# ProProject_AT_START_L021_V1_0.net
KiCad netlist of a schematic drawn in EasyEDA Pro
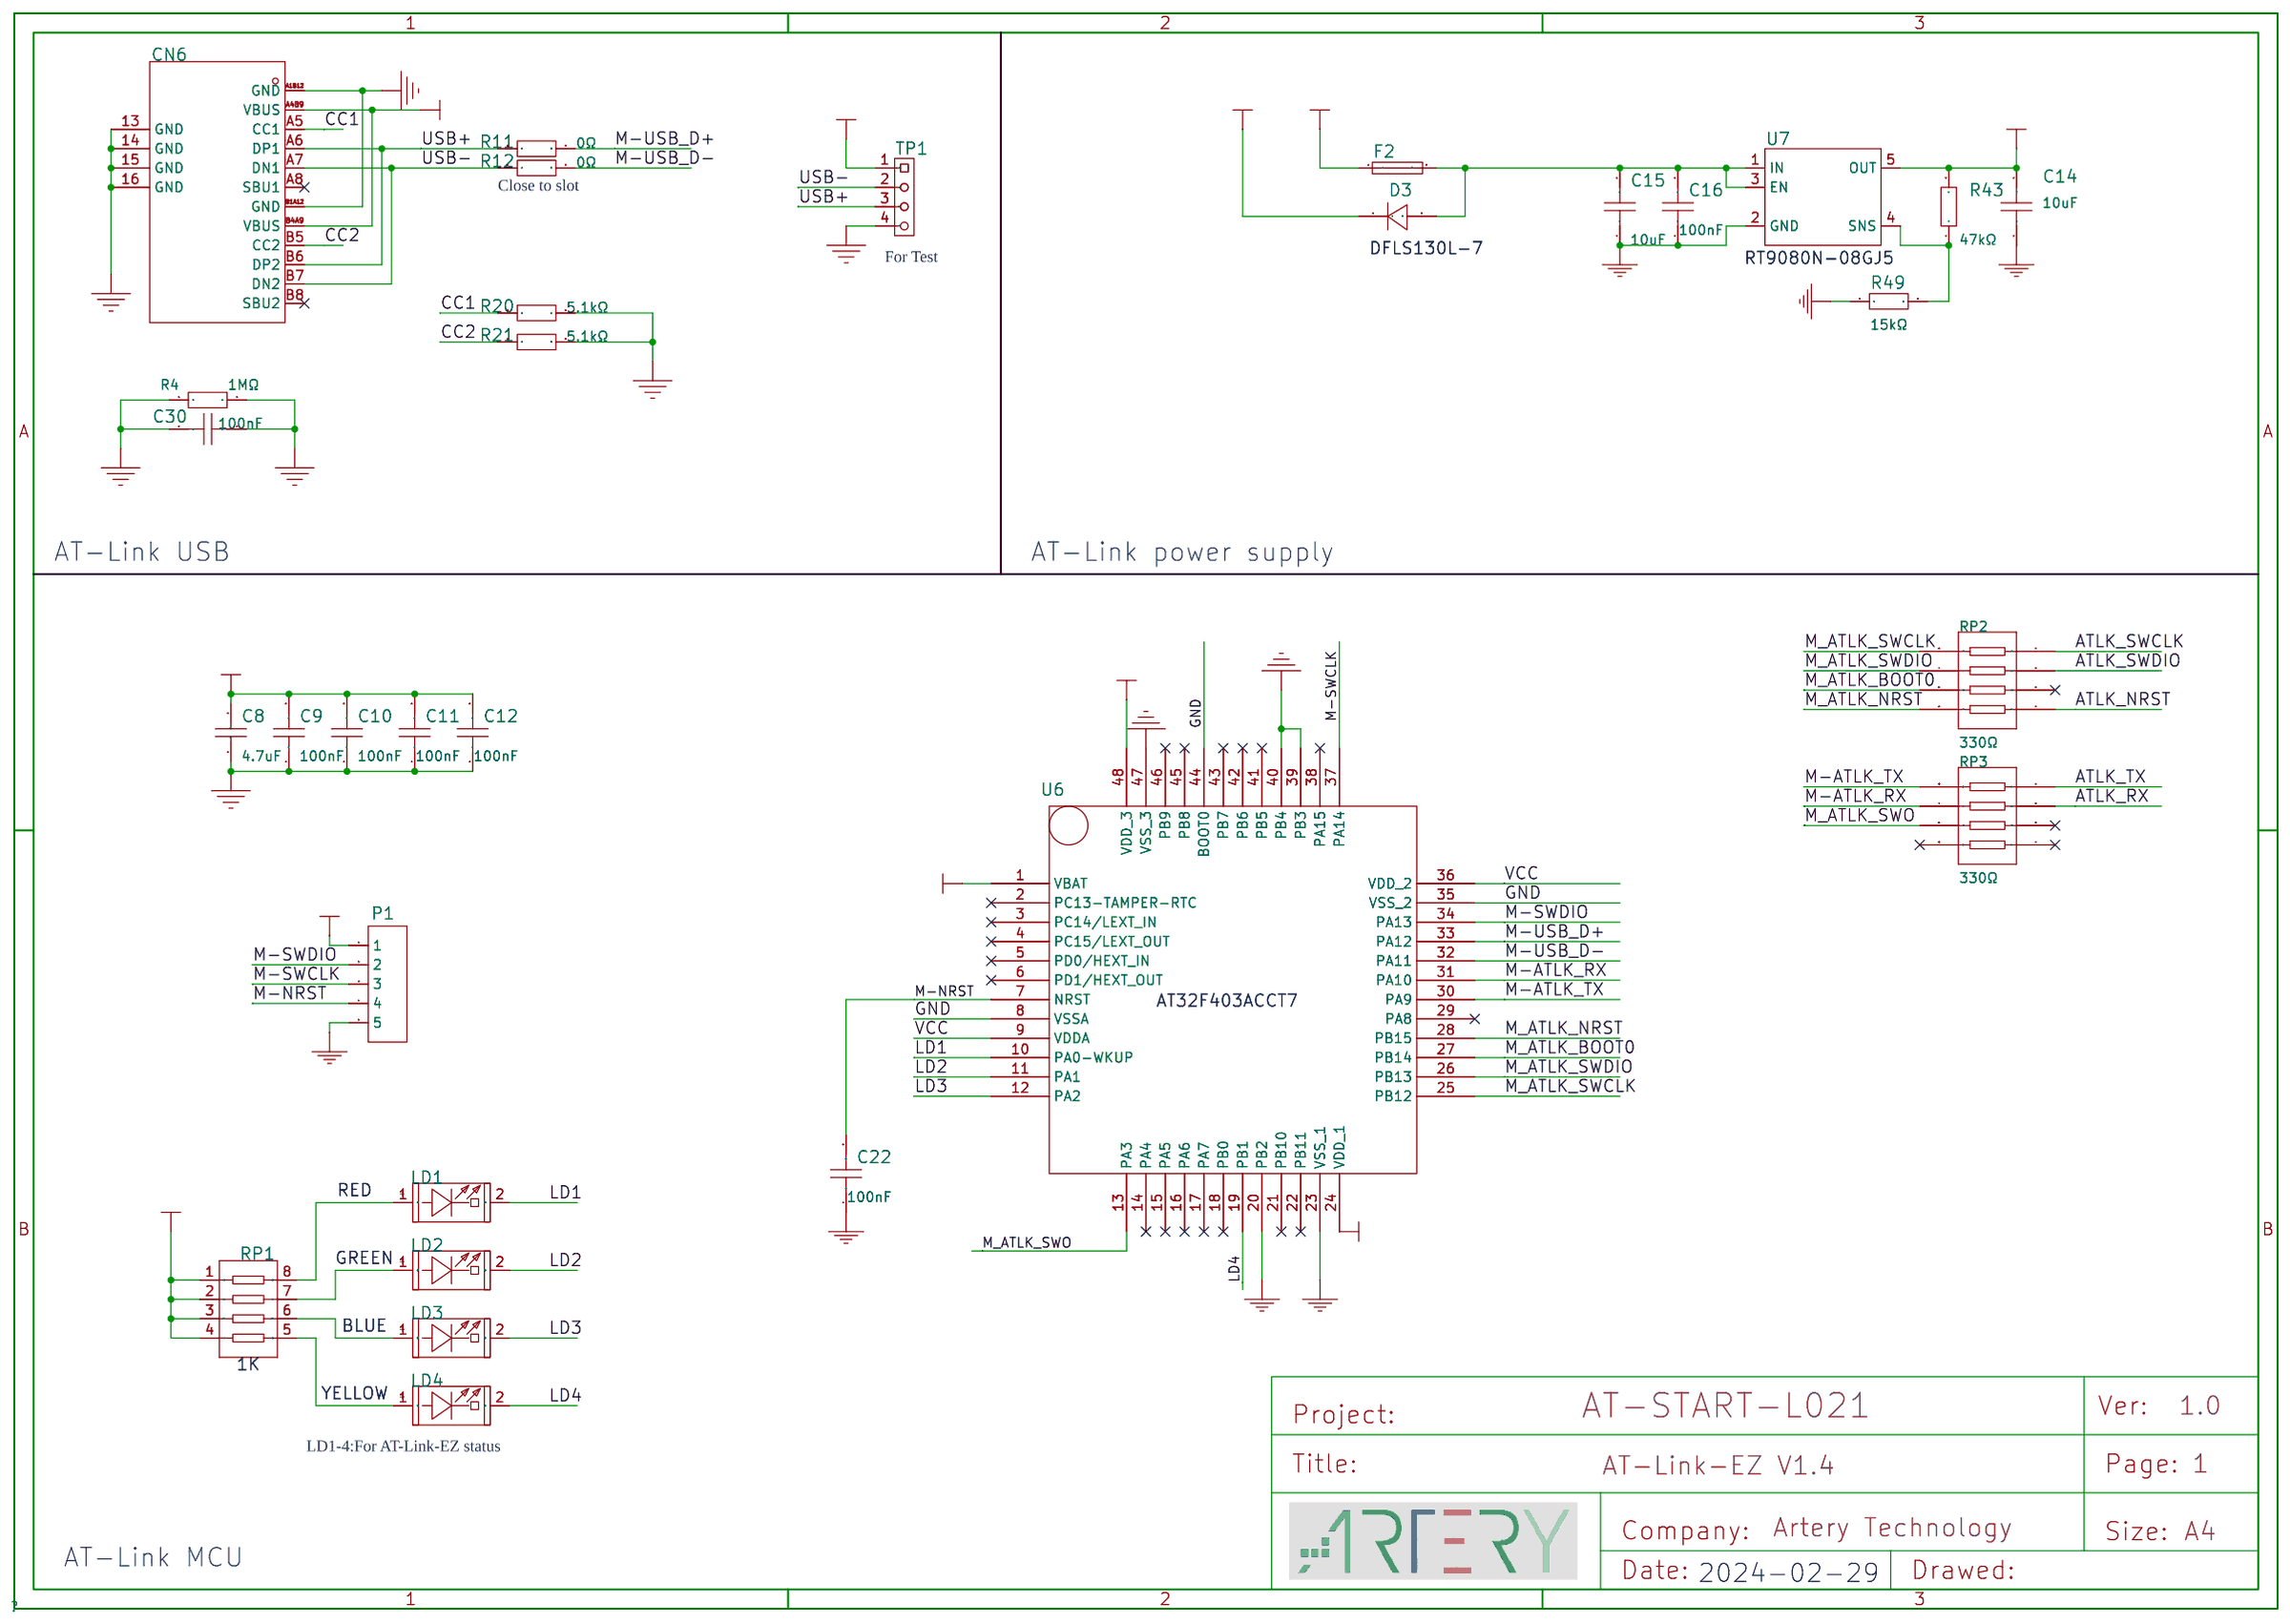
[diagram p0: AT-Link-EZ V1.4]
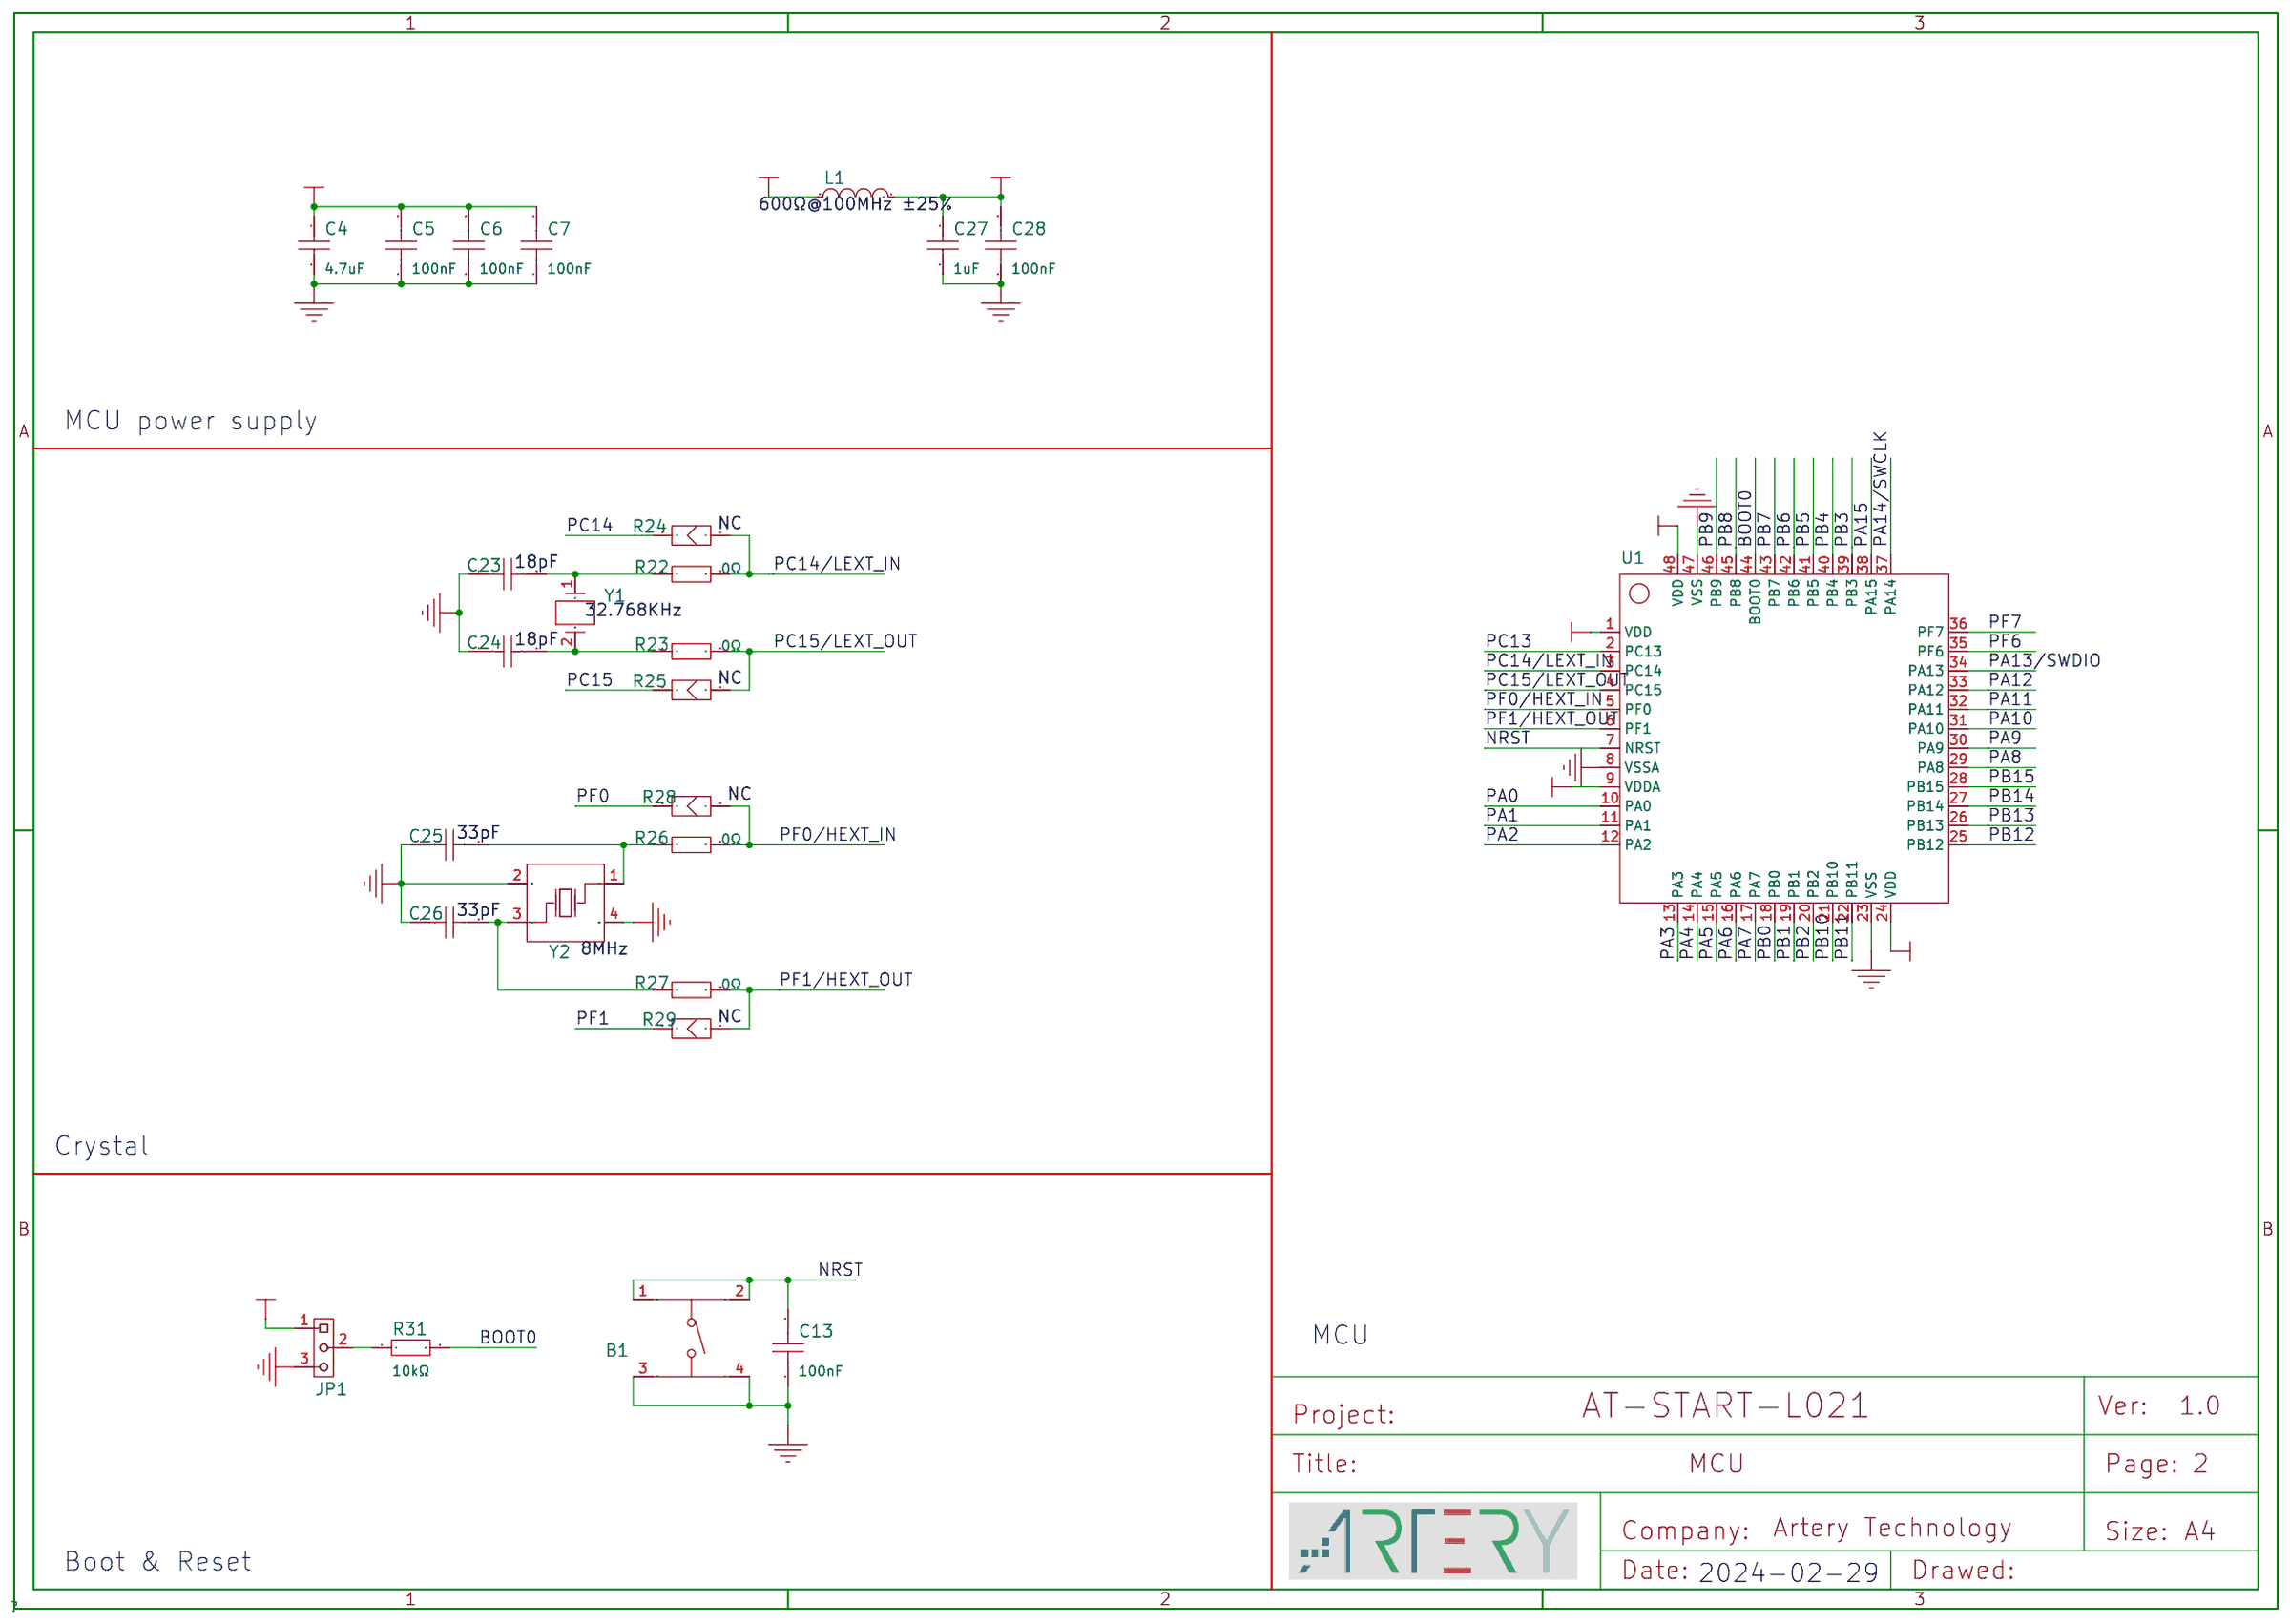
[diagram p1: MCU]
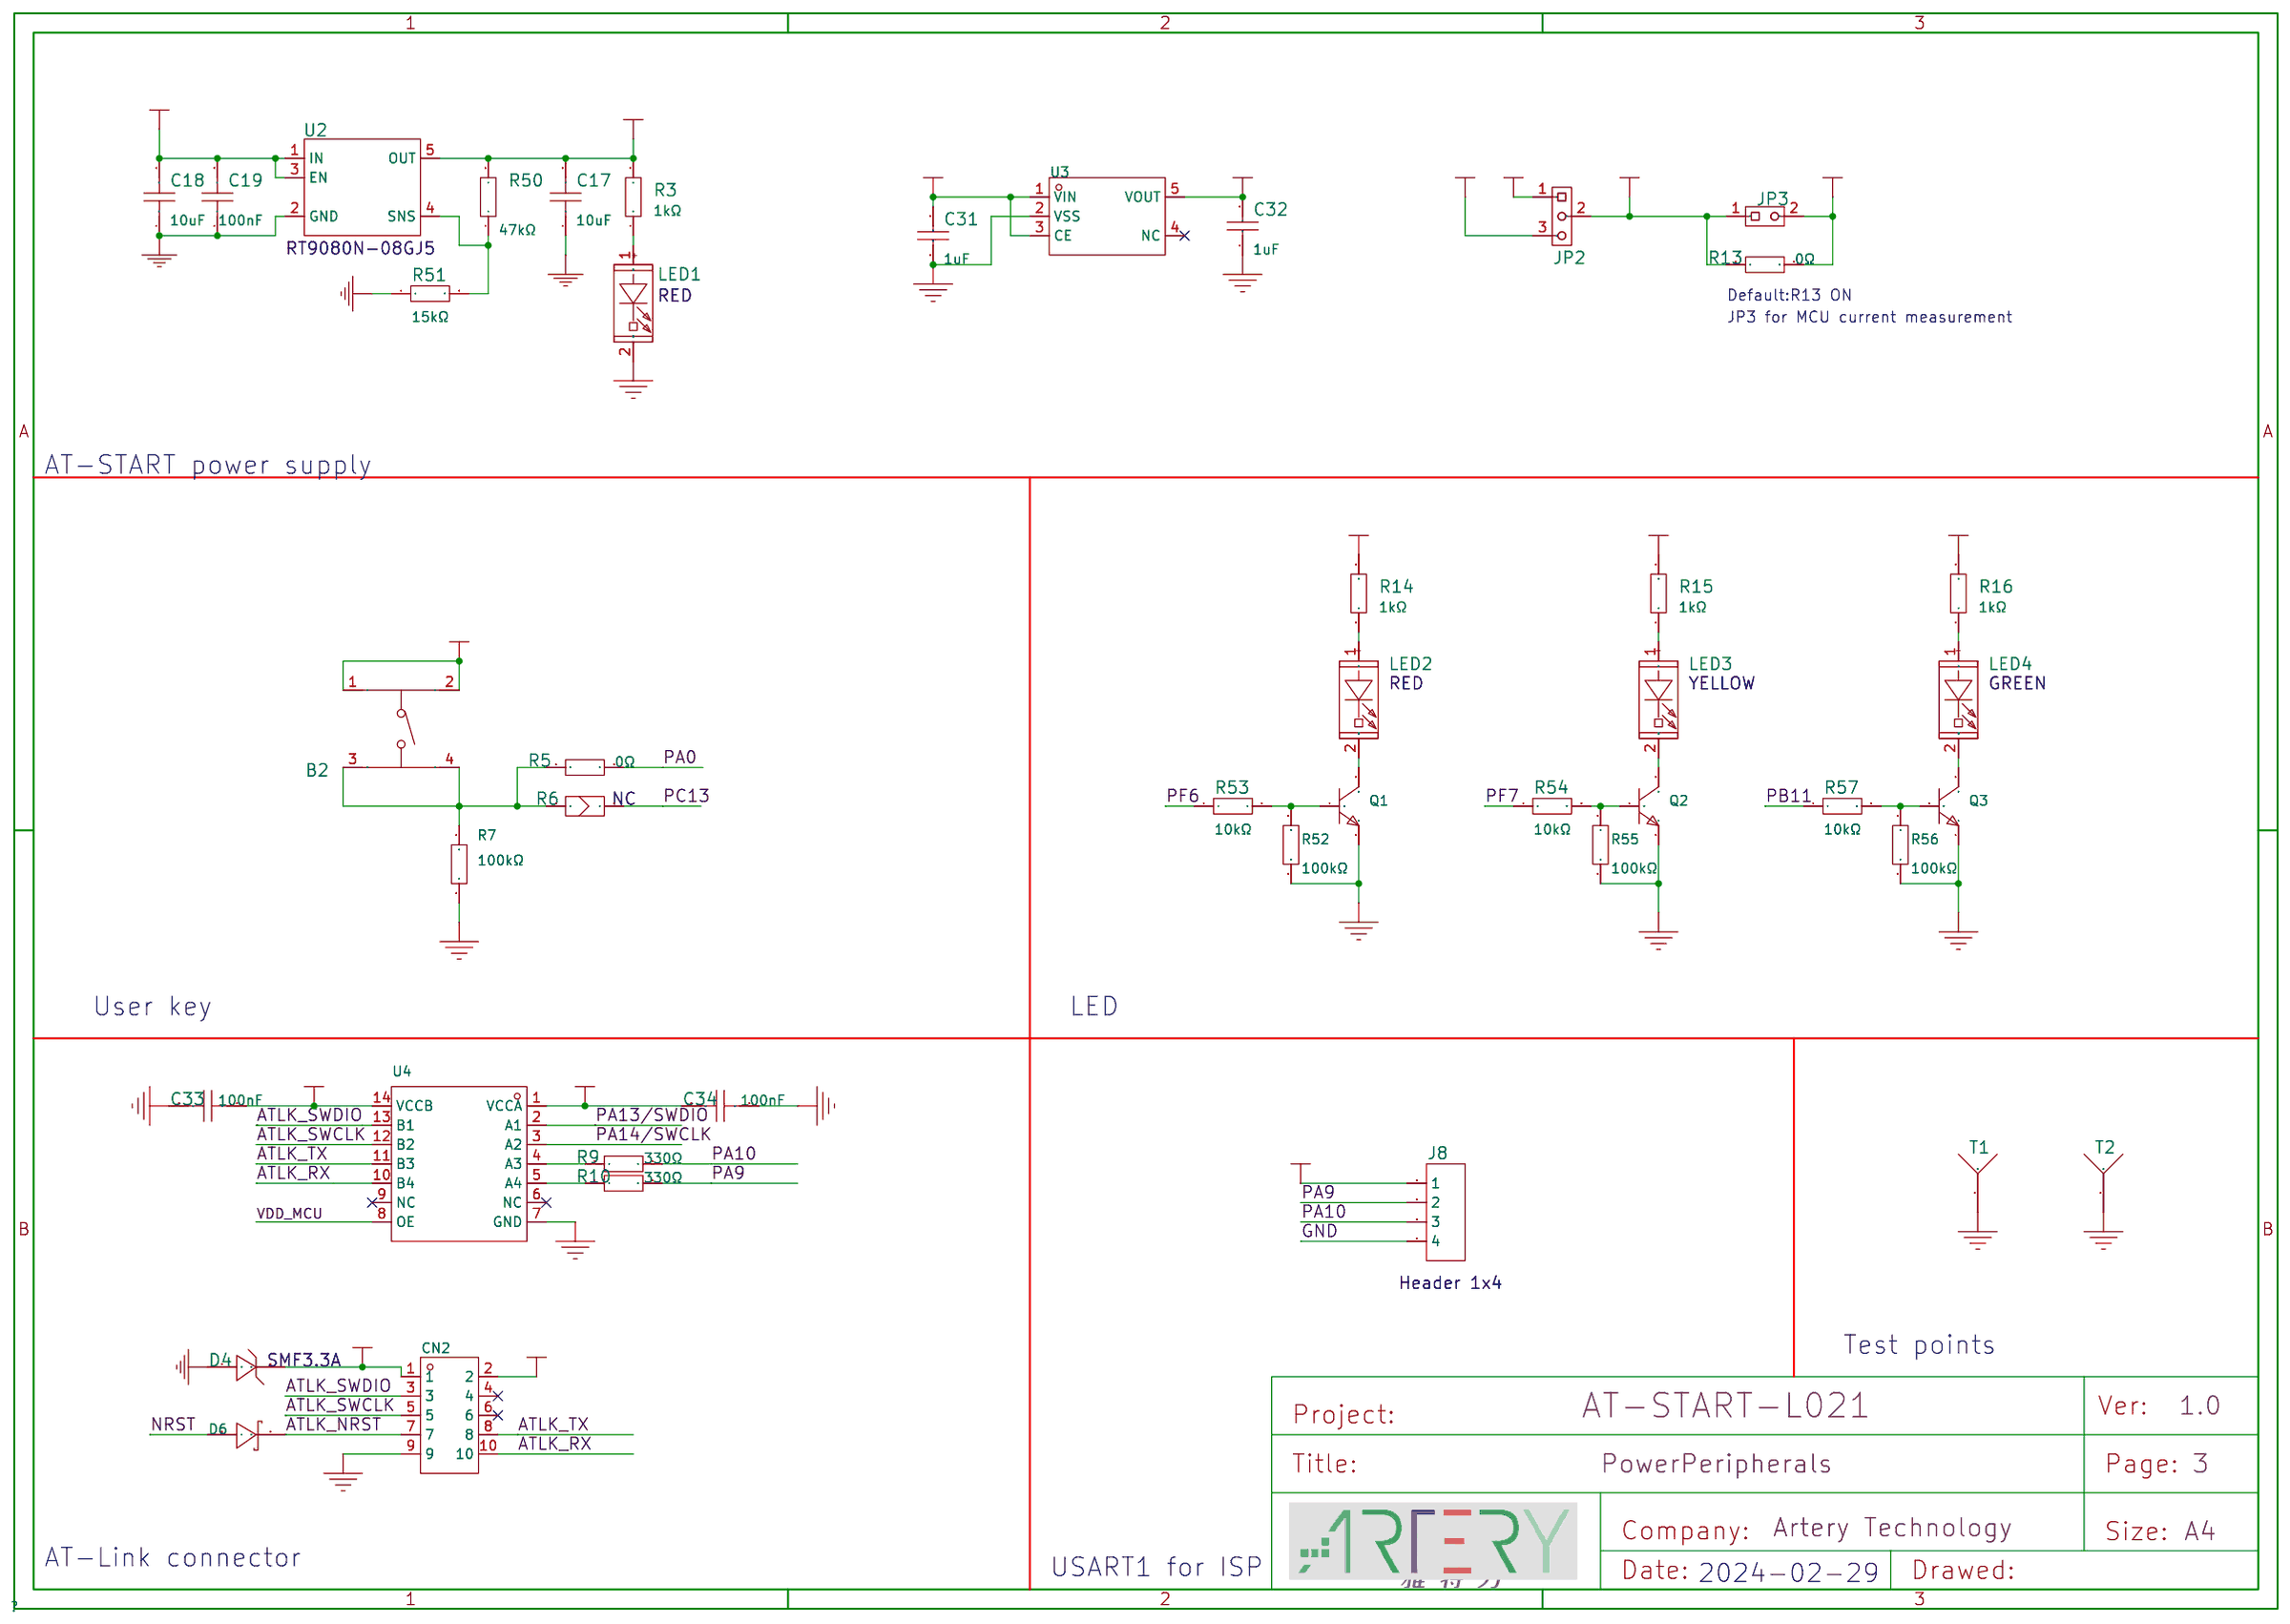
[diagram p2: PowerPeripherals]
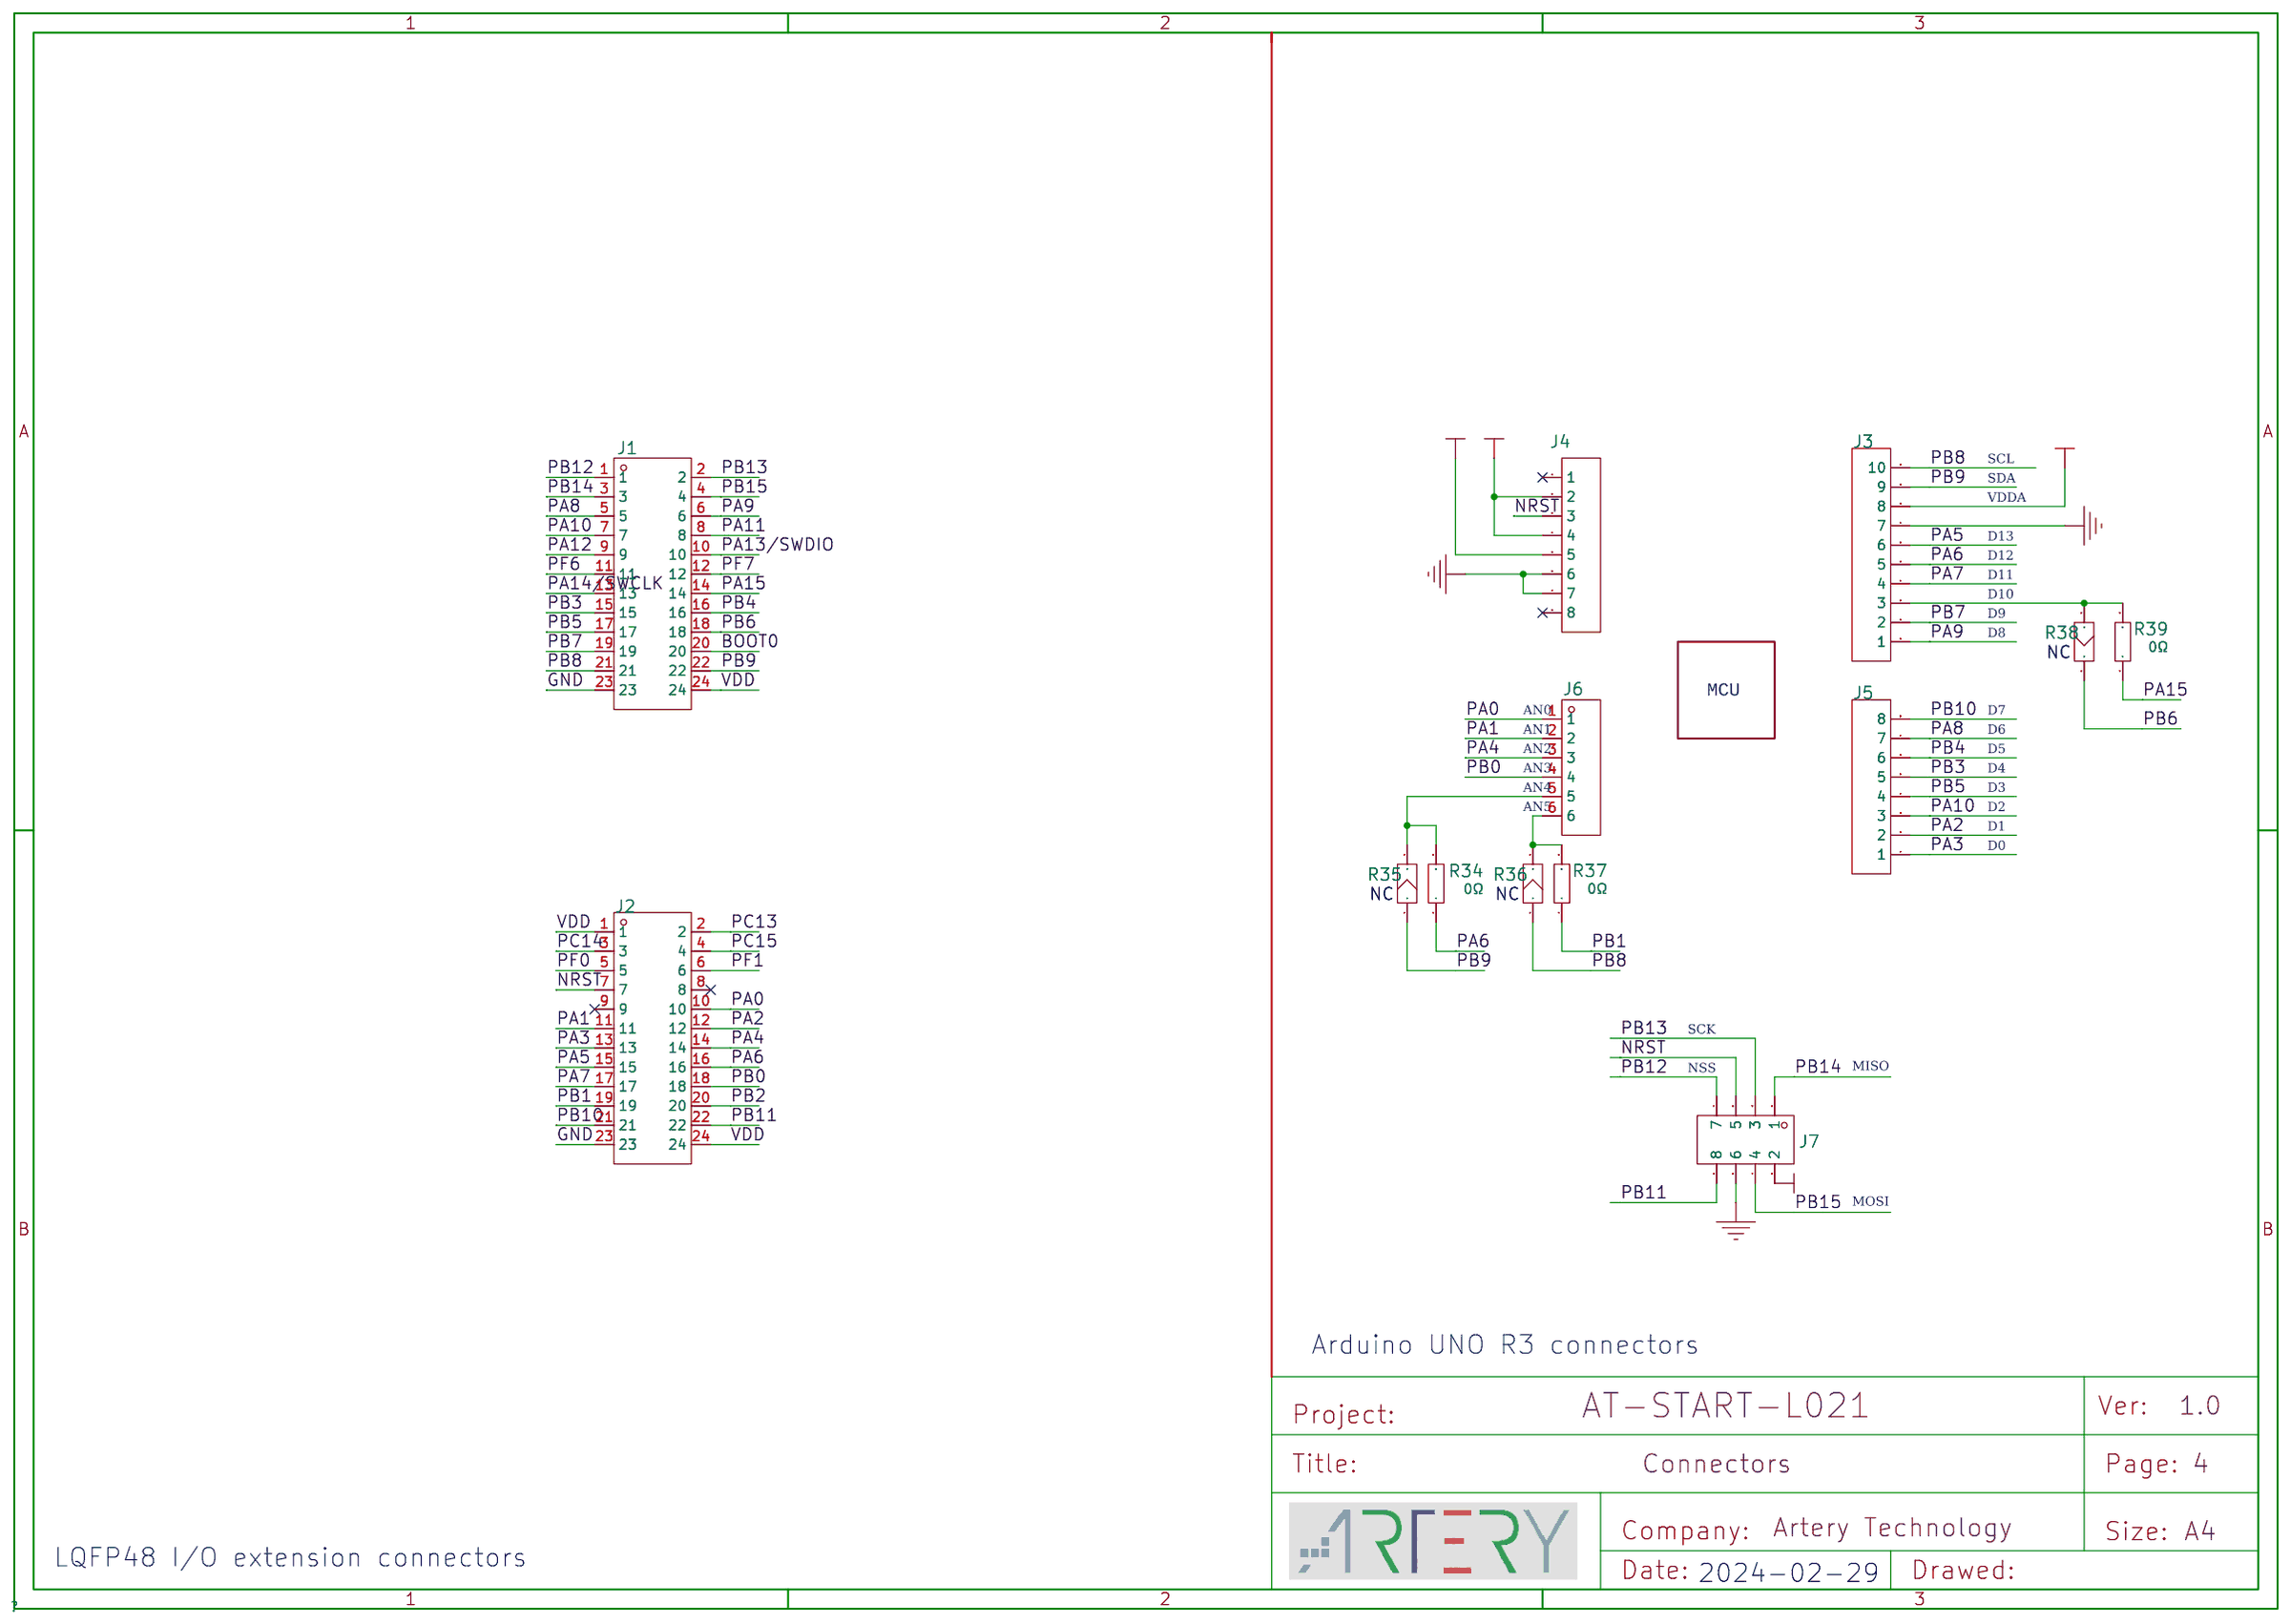
[diagram p3: Connectors]

(export (version "E")
  (design (tool "Eeschema 10.0.6"))
  (components
    (comp (ref "C8")
      (value "4.7uF")
      (footprint "easyedapro:C0603")
      (description "容值:4.7uF;精度:±10%;额定电压:16V;温度系数:X5R;")
      (fields
        (field (name "Manufacturer Part") "CL10A475KO8NNNC")
        (field (name "Manufacturer") "SAMSUNG(三星)")
      )
      (libsource (lib "easyedapro") (part "CL10A475KO8NNNC"))
    )
    (comp (ref "C9")
      (value "100nF")
      (footprint "easyedapro:C0603")
      (description "容值:100nF;精度:±10%;额定电压:50V;温度系数:X7R;")
      (fields
        (field (name "Manufacturer Part") "CC0603KRX7R9BB104")
        (field (name "Manufacturer") "YAGEO(国巨)")
      )
      (libsource (lib "easyedapro") (part "CC0603KRX7R9BB104"))
    )
    (comp (ref "C10")
      (value "100nF")
      (footprint "easyedapro:C0603")
      (description "容值:100nF;精度:±10%;额定电压:50V;温度系数:X7R;")
      (fields
        (field (name "Manufacturer Part") "CC0603KRX7R9BB104")
        (field (name "Manufacturer") "YAGEO(国巨)")
      )
      (libsource (lib "easyedapro") (part "CC0603KRX7R9BB104"))
    )
    (comp (ref "C11")
      (value "100nF")
      (footprint "easyedapro:C0603")
      (description "容值:100nF;精度:±10%;额定电压:50V;温度系数:X7R;")
      (fields
        (field (name "Manufacturer Part") "CC0603KRX7R9BB104")
        (field (name "Manufacturer") "YAGEO(国巨)")
      )
      (libsource (lib "easyedapro") (part "CC0603KRX7R9BB104"))
    )
    (comp (ref "C12")
      (value "100nF")
      (footprint "easyedapro:C0603")
      (description "容值:100nF;精度:±10%;额定电压:50V;温度系数:X7R;")
      (fields
        (field (name "Manufacturer Part") "CC0603KRX7R9BB104")
        (field (name "Manufacturer") "YAGEO(国巨)")
      )
      (libsource (lib "easyedapro") (part "CC0603KRX7R9BB104"))
    )
    (comp (ref "C14")
      (value "10uF")
      (footprint "easyedapro:C0603")
      (description "容值:10uF;精度:±10%;额定电压:10V;温度系数:X5R;")
      (fields
        (field (name "Manufacturer Part") "CL10A106KP8NNNC")
        (field (name "Manufacturer") "SAMSUNG(三星)")
      )
      (libsource (lib "easyedapro") (part "CL10A106KP8NNNC"))
    )
    (comp (ref "C15")
      (value "10uF")
      (footprint "easyedapro:C0603")
      (description "容值:10uF;精度:±10%;额定电压:10V;温度系数:X5R;")
      (fields
        (field (name "Manufacturer Part") "CL10A106KP8NNNC")
        (field (name "Manufacturer") "SAMSUNG(三星)")
      )
      (libsource (lib "easyedapro") (part "CL10A106KP8NNNC"))
    )
    (comp (ref "C16")
      (value "100nF")
      (footprint "easyedapro:C0603")
      (description "容值:100nF;精度:±10%;额定电压:50V;温度系数:X7R;")
      (fields
        (field (name "Manufacturer Part") "CC0603KRX7R9BB104")
        (field (name "Manufacturer") "YAGEO(国巨)")
      )
      (libsource (lib "easyedapro") (part "CC0603KRX7R9BB104"))
    )
    (comp (ref "C22")
      (value "100nF")
      (footprint "easyedapro:C0603")
      (description "容值:100nF;精度:±10%;额定电压:50V;温度系数:X7R;")
      (fields
        (field (name "Manufacturer Part") "CC0603KRX7R9BB104")
        (field (name "Manufacturer") "YAGEO(国巨)")
      )
      (libsource (lib "easyedapro") (part "CC0603KRX7R9BB104"))
    )
    (comp (ref "C30")
      (value "100nF")
      (footprint "easyedapro:C0603")
      (description "容值:100nF;精度:±10%;额定电压:50V;温度系数:X7R;")
      (fields
        (field (name "Manufacturer Part") "CC0603KRX7R9BB104")
        (field (name "Manufacturer") "YAGEO(国巨)")
      )
      (libsource (lib "easyedapro") (part "CC0603KRX7R9BB104"))
    )
    (comp (ref "CN6")
      (value "~")
      (footprint "easyedapro:USB-C-SMD_TYPEC-304-BCP16")
      (description "连接器类型:Type-C;标准:USB 3.1;公母:母座;触点数量:16.0;端口数量:1;安装方式:卧贴;额定电流 - 电源:3A;工作温度范围:-25~+85;焊接温度(最大值):260;")
      (fields (field (name "Manufacturer Part") "TYPEC-304-BCP16") (field (name "Manufacturer") "XUNPU(讯普)"))
      (libsource (lib "easyedapro") (part "TYPEC-304-BCP16"))
    )
    (comp (ref "D3")
      (value "DFLS130L-7")
      (footprint "easyedapro:POWERDI-123_L2.8-W1.8-LS3.7-RD(1)")
      (fields (field (name "Manufacturer") "Diodes Incorporated"))
      (libsource (lib "easyedapro") (part "DFLS130L-7"))
    )
    (comp (ref "F2")
      (value "SMD0603B050TF")
      (footprint "easyedapro:R0603")
      (fields
        (field (name "Manufacturer Part") "SMD0603B035TF")
        (field (name "Manufacturer") "Brightking Elec (TAIWAN)")
      )
      (libsource (lib "easyedapro") (part "SMD0603B050TF"))
    )
    (comp (ref "LD1")
      (value "RED")
      (footprint "easyedapro:LED0603")
      (libsource (lib "easyedapro") (part "RED"))
    )
    (comp (ref "LD2")
      (value "GREEN")
      (footprint "easyedapro:LED0603")
      (libsource (lib "easyedapro") (part "GREEN"))
    )
    (comp (ref "LD3")
      (value "BLUE")
      (footprint "easyedapro:LED0603")
      (libsource (lib "easyedapro") (part "BLUE"))
    )
    (comp (ref "LD4")
      (value "YELLOW")
      (footprint "easyedapro:LED0603")
      (libsource (lib "easyedapro") (part "YELLOW"))
    )
    (comp (ref "P1")
      (value "HDR-M-2.54_1x5")
      (footprint "easyedapro:HDR-M-2.54_1X5")
      (libsource (lib "easyedapro") (part "HDR-M-2.54_1x5"))
    )
    (comp (ref "R4")
      (value "1MΩ")
      (footprint "easyedapro:R0603")
      (description "阻值:1MΩ;精度:±1%;功率:100mW;温度系数:±100ppm/;最大工作电压:75V;工作温度范围:-55~+155;")
      (fields (field (name "Manufacturer Part") "RC0603FR-071ML") (field (name "Manufacturer") "YAGEO(国巨)"))
      (libsource (lib "easyedapro") (part "RC0603FR-071ML"))
    )
    (comp (ref "R11")
      (value "0Ω")
      (footprint "easyedapro:R0603")
      (description "电阻类型:厚膜电阻;阻值:0Ω;精度:±1%;功率:1/10W;温度系数:-;最大工作电压:75V;工作温度范围:-55~+155;")
      (fields
        (field (name "Manufacturer Part") "0603WAF0000T5E")
        (field (name "Manufacturer") "UNI-ROYAL(厚声)")
      )
      (libsource (lib "easyedapro") (part "0603WAF0000T5E"))
    )
    (comp (ref "R12")
      (value "0Ω")
      (footprint "easyedapro:R0603")
      (description "电阻类型:厚膜电阻;阻值:0Ω;精度:±1%;功率:1/10W;温度系数:-;最大工作电压:75V;工作温度范围:-55~+155;")
      (fields
        (field (name "Manufacturer Part") "0603WAF0000T5E")
        (field (name "Manufacturer") "UNI-ROYAL(厚声)")
      )
      (libsource (lib "easyedapro") (part "0603WAF0000T5E"))
    )
    (comp (ref "R20")
      (value "5.1kΩ")
      (footprint "easyedapro:R0603")
      (description "电阻类型:厚膜电阻;阻值:5.1kΩ;精度:±1%;功率:1/10W;温度系数:±100ppm/;最大工作电压:75V;工作温度范围:-55~+155;")
      (fields
        (field (name "Manufacturer Part") "0603WAF5101T5E")
        (field (name "Manufacturer") "UNI-ROYAL(厚声)")
      )
      (libsource (lib "easyedapro") (part "0603WAF5101T5E"))
    )
    (comp (ref "R21")
      (value "5.1kΩ")
      (footprint "easyedapro:R0603")
      (description "电阻类型:厚膜电阻;阻值:5.1kΩ;精度:±1%;功率:1/10W;温度系数:±100ppm/;最大工作电压:75V;工作温度范围:-55~+155;")
      (fields
        (field (name "Manufacturer Part") "0603WAF5101T5E")
        (field (name "Manufacturer") "UNI-ROYAL(厚声)")
      )
      (libsource (lib "easyedapro") (part "0603WAF5101T5E"))
    )
    (comp (ref "R43")
      (value "47kΩ")
      (footprint "easyedapro:R0603")
      (description "电阻类型:厚膜电阻;阻值:47kΩ;精度:±1%;功率:1/10W;温度系数:±100ppm/;最大工作电压:75V;工作温度范围:-55~+155;")
      (fields
        (field (name "Manufacturer Part") "0603WAF4702T5E")
        (field (name "Manufacturer") "UNI-ROYAL(厚声)")
      )
      (libsource (lib "easyedapro") (part "0603WAF4702T5E"))
    )
    (comp (ref "R49")
      (value "15kΩ")
      (footprint "easyedapro:R0603")
      (description "电阻类型:厚膜电阻;阻值:15kΩ;精度:±1%;功率:1/10W;温度系数:±100ppm/;最大工作电压:75V;工作温度范围:-55~+155;")
      (fields
        (field (name "Manufacturer Part") "0603WAF1502T5E")
        (field (name "Manufacturer") "UNI-ROYAL(厚声)")
      )
      (libsource (lib "easyedapro") (part "0603WAF1502T5E"))
    )
    (comp (ref "RP1")
      (value "1K")
      (footprint "easyedapro:0603*4,8P4R")
      (fields (field (name "Comment") "33R"))
      (libsource (lib "easyedapro") (part "1K"))
    )
    (comp (ref "RP2")
      (value "330Ω")
      (footprint "easyedapro:RES-ARRAY-SMD_0603-8P-L3.2-W1.6-BL")
      (description "阻值:330Ω;精度:±5%;单个元件功率:62.5mW;电阻器数:4;温度系数:±200ppm/°C;")
      (fields
        (field (name "Manufacturer Part") "4D03WGJ0331T5E")
        (field (name "Manufacturer") "UNI-ROYAL(厚声)")
      )
      (libsource (lib "easyedapro") (part "4D03WGJ0331T5E"))
    )
    (comp (ref "RP3")
      (value "330Ω")
      (footprint "easyedapro:RES-ARRAY-SMD_0603-8P-L3.2-W1.6-BL")
      (description "阻值:330Ω;精度:±5%;单个元件功率:62.5mW;电阻器数:4;温度系数:±200ppm/°C;")
      (fields
        (field (name "Manufacturer Part") "4D03WGJ0331T5E")
        (field (name "Manufacturer") "UNI-ROYAL(厚声)")
      )
      (libsource (lib "easyedapro") (part "4D03WGJ0331T5E"))
    )
    (comp (ref "TP1")
      (value "1X4P_2.54F")
      (footprint "easyedapro:HDR1X4 - TOP")
      (libsource (lib "easyedapro") (part "1X4P_2.54F"))
    )
    (comp (ref "U6")
      (value "AT32F403ACCT7")
      (footprint "easyedapro:LQFP48 - 2")
      (libsource (lib "easyedapro") (part "AT32F403CGT6"))
    )
    (comp (ref "U7")
      (value "RT9080N-08GJ5")
      (footprint "easyedapro:SOT-23-5")
      (libsource (lib "easyedapro") (part "RT9080N-08GJ5"))
    )
    (comp (ref "B1")
      (value "K2-1102SP-C4SC-04")
      (footprint "easyedapro:KEY-SMD_4P-L6.0-W6.0-P4.50-LS9.5-BL")
      (fields (field (name "Manufacturer") "韩国韩荣"))
      (libsource (lib "easyedapro") (part "K2-1102SP-C4SC-04"))
    )
    (comp (ref "C4")
      (value "4.7uF")
      (footprint "easyedapro:C0603")
      (description "容值:4.7uF;精度:±10%;额定电压:16V;温度系数:X5R;")
      (fields
        (field (name "Manufacturer Part") "CL10A475KO8NNNC")
        (field (name "Manufacturer") "SAMSUNG(三星)")
      )
      (libsource (lib "easyedapro") (part "CL10A475KO8NNNC"))
    )
    (comp (ref "C5")
      (value "100nF")
      (footprint "easyedapro:C0603")
      (description "容值:100nF;精度:±10%;额定电压:50V;温度系数:X7R;")
      (fields
        (field (name "Manufacturer Part") "CC0603KRX7R9BB104")
        (field (name "Manufacturer") "YAGEO(国巨)")
      )
      (libsource (lib "easyedapro") (part "CC0603KRX7R9BB104"))
    )
    (comp (ref "C6")
      (value "100nF")
      (footprint "easyedapro:C0603")
      (description "容值:100nF;精度:±10%;额定电压:50V;温度系数:X7R;")
      (fields
        (field (name "Manufacturer Part") "CC0603KRX7R9BB104")
        (field (name "Manufacturer") "YAGEO(国巨)")
      )
      (libsource (lib "easyedapro") (part "CC0603KRX7R9BB104"))
    )
    (comp (ref "C7")
      (value "100nF")
      (footprint "easyedapro:C0603")
      (description "容值:100nF;精度:±10%;额定电压:50V;温度系数:X7R;")
      (fields
        (field (name "Manufacturer Part") "CC0603KRX7R9BB104")
        (field (name "Manufacturer") "YAGEO(国巨)")
      )
      (libsource (lib "easyedapro") (part "CC0603KRX7R9BB104"))
    )
    (comp (ref "C13")
      (value "100nF")
      (footprint "easyedapro:C0603")
      (description "容值:100nF;精度:±10%;额定电压:50V;温度系数:X7R;")
      (fields
        (field (name "Manufacturer Part") "CC0603KRX7R9BB104")
        (field (name "Manufacturer") "YAGEO(国巨)")
      )
      (libsource (lib "easyedapro") (part "CC0603KRX7R9BB104"))
    )
    (comp (ref "C23")
      (value "18pF")
      (footprint "easyedapro:0603_C-M")
      (fields
        (field (name "Manufacturer Part") "CL10C180JB8NNNC")
        (field (name "Manufacturer") "SAMSUNG(三星)")
      )
      (libsource (lib "easyedapro") (part "10pF"))
    )
    (comp (ref "C24")
      (value "18pF")
      (footprint "easyedapro:0603_C-M")
      (fields
        (field (name "Manufacturer Part") "CL10C180JB8NNNC")
        (field (name "Manufacturer") "SAMSUNG(三星)")
      )
      (libsource (lib "easyedapro") (part "10pF"))
    )
    (comp (ref "C25")
      (value "33pF")
      (footprint "easyedapro:0603_C-M(1)")
      (fields
        (field (name "Manufacturer Part") "CL10C330JB8NNNC")
        (field (name "Manufacturer") "SAMSUNG(三星)")
      )
      (libsource (lib "easyedapro") (part "22pF"))
    )
    (comp (ref "C26")
      (value "33pF")
      (footprint "easyedapro:0603_C-M(1)")
      (fields
        (field (name "Manufacturer Part") "CL10C330JB8NNNC")
        (field (name "Manufacturer") "SAMSUNG(三星)")
      )
      (libsource (lib "easyedapro") (part "22pF"))
    )
    (comp (ref "C27")
      (value "1uF")
      (footprint "easyedapro:C0603")
      (description "容值:1uF;精度:±10%;额定电压:50V;温度系数:X5R;")
      (fields
        (field (name "Manufacturer Part") "CL10A105KB8NNNC")
        (field (name "Manufacturer") "SAMSUNG(三星)")
      )
      (libsource (lib "easyedapro") (part "CL10A105KB8NNNC"))
    )
    (comp (ref "C28")
      (value "100nF")
      (footprint "easyedapro:C0603")
      (description "容值:100nF;精度:±10%;额定电压:50V;温度系数:X7R;")
      (fields
        (field (name "Manufacturer Part") "CC0603KRX7R9BB104")
        (field (name "Manufacturer") "YAGEO(国巨)")
      )
      (libsource (lib "easyedapro") (part "CC0603KRX7R9BB104"))
    )
    (comp (ref "JP1")
      (value "Header 1x3")
      (footprint "easyedapro:HEADER 1X3")
      (libsource (lib "easyedapro") (part "Header 1x3"))
    )
    (comp (ref "L1")
      (value "600Ω@100MHz ±25%")
      (footprint "easyedapro:L0603")
      (description "标称阻抗@测试频率:600Ω@100MHz;误差:±25%;直流电阻(RDC):150mΩ;额定电流:1A;电路数:1;")
      (fields
        (field (name "Manufacturer Part") "UPZ1608E601-1R0TF")
        (field (name "Manufacturer") "Sunlord(顺络)")
      )
      (libsource (lib "easyedapro") (part "UPZ1608E601-1R0TF"))
    )
    (comp (ref "R22")
      (value "0Ω")
      (footprint "easyedapro:R0603")
      (description "电阻类型:厚膜电阻;阻值:0Ω;精度:±1%;功率:1/10W;温度系数:-;最大工作电压:75V;工作温度范围:-55~+155;")
      (fields
        (field (name "Manufacturer Part") "0603WAF0000T5E")
        (field (name "Manufacturer") "UNI-ROYAL(厚声)")
      )
      (libsource (lib "easyedapro") (part "0603WAF0000T5E"))
    )
    (comp (ref "R23")
      (value "0Ω")
      (footprint "easyedapro:R0603")
      (description "电阻类型:厚膜电阻;阻值:0Ω;精度:±1%;功率:1/10W;温度系数:-;最大工作电压:75V;工作温度范围:-55~+155;")
      (fields
        (field (name "Manufacturer Part") "0603WAF0000T5E")
        (field (name "Manufacturer") "UNI-ROYAL(厚声)")
      )
      (libsource (lib "easyedapro") (part "0603WAF0000T5E"))
    )
    (comp (ref "R24") (value "NC") (footprint "easyedapro:SB-PAD") (libsource (lib "easyedapro") (part "NC")))
    (comp (ref "R25") (value "NC") (footprint "easyedapro:SB-PAD") (libsource (lib "easyedapro") (part "NC")))
    (comp (ref "R26")
      (value "0Ω")
      (footprint "easyedapro:R0603")
      (description "电阻类型:厚膜电阻;阻值:0Ω;精度:±1%;功率:1/10W;温度系数:-;最大工作电压:75V;工作温度范围:-55~+155;")
      (fields
        (field (name "Manufacturer Part") "0603WAF0000T5E")
        (field (name "Manufacturer") "UNI-ROYAL(厚声)")
      )
      (libsource (lib "easyedapro") (part "0603WAF0000T5E"))
    )
    (comp (ref "R27")
      (value "0Ω")
      (footprint "easyedapro:R0603")
      (description "电阻类型:厚膜电阻;阻值:0Ω;精度:±1%;功率:1/10W;温度系数:-;最大工作电压:75V;工作温度范围:-55~+155;")
      (fields
        (field (name "Manufacturer Part") "0603WAF0000T5E")
        (field (name "Manufacturer") "UNI-ROYAL(厚声)")
      )
      (libsource (lib "easyedapro") (part "0603WAF0000T5E"))
    )
    (comp (ref "R28") (value "NC") (footprint "easyedapro:SB-PAD") (libsource (lib "easyedapro") (part "NC")))
    (comp (ref "R29") (value "NC") (footprint "easyedapro:SB-PAD") (libsource (lib "easyedapro") (part "NC")))
    (comp (ref "R31")
      (value "10kΩ")
      (footprint "easyedapro:R0603")
      (description "电阻类型:厚膜电阻;阻值:10kΩ;精度:±1%;功率:1/10W;温度系数:±100ppm/;最大工作电压:75V;工作温度范围:-55~+155;")
      (fields
        (field (name "Manufacturer Part") "0603WAF1002T5E")
        (field (name "Manufacturer") "UNI-ROYAL(厚声)")
      )
      (libsource (lib "easyedapro") (part "0603WAF1002T5E"))
    )
    (comp (ref "U1")
      (value "~")
      (footprint "easyedapro:LQFP-48_L7.0-W7.0-P0.50-LS9.0-BL")
      (fields (field (name "Manufacturer Part") "AT32L021C8T7") (field (name "Manufacturer") "ARTERY（雅特力）"))
      (libsource (lib "easyedapro") (part "AT32L021C8T7"))
    )
    (comp (ref "Y1")
      (value "32.768KHz")
      (footprint "easyedapro:XTAL_SOP - FC-12M")
      (libsource (lib "easyedapro") (part "32.768KHz"))
    )
    (comp (ref "Y2")
      (value "8MHz")
      (footprint "easyedapro:OSC-SMD_4P-L5.0-W3.2-BL")
      (fields (field (name "Manufacturer Part") "X50328MSD4SC") (field (name "Manufacturer") "YXC"))
      (libsource (lib "easyedapro") (part "8MHz"))
    )
    (comp (ref "B2")
      (value "蓝色")
      (footprint "easyedapro:KEY-SMD_4P-L6.0-W6.0-P4.50-LS9.5-BL")
      (fields (field (name "Manufacturer") "韩国韩荣"))
      (libsource (lib "easyedapro") (part "K2-1102SP-C4SC-04"))
    )
    (comp (ref "C17")
      (value "10uF")
      (footprint "easyedapro:C0603")
      (description "容值:10uF;精度:±10%;额定电压:10V;温度系数:X5R;")
      (fields
        (field (name "Manufacturer Part") "CL10A106KP8NNNC")
        (field (name "Manufacturer") "SAMSUNG(三星)")
      )
      (libsource (lib "easyedapro") (part "CL10A106KP8NNNC"))
    )
    (comp (ref "C18")
      (value "10uF")
      (footprint "easyedapro:C0603")
      (description "容值:10uF;精度:±10%;额定电压:10V;温度系数:X5R;")
      (fields
        (field (name "Manufacturer Part") "CL10A106KP8NNNC")
        (field (name "Manufacturer") "SAMSUNG(三星)")
      )
      (libsource (lib "easyedapro") (part "CL10A106KP8NNNC"))
    )
    (comp (ref "C19")
      (value "100nF")
      (footprint "easyedapro:C0603")
      (description "容值:100nF;精度:±10%;额定电压:50V;温度系数:X7R;")
      (fields
        (field (name "Manufacturer Part") "CC0603KRX7R9BB104")
        (field (name "Manufacturer") "YAGEO(国巨)")
      )
      (libsource (lib "easyedapro") (part "CC0603KRX7R9BB104"))
    )
    (comp (ref "C31")
      (value "1uF")
      (footprint "easyedapro:C0603")
      (description "容值:1uF;精度:±10%;额定电压:50V;温度系数:X5R;")
      (fields
        (field (name "Manufacturer Part") "CL10A105KB8NNNC")
        (field (name "Manufacturer") "SAMSUNG(三星)")
      )
      (libsource (lib "easyedapro") (part "CL10A105KB8NNNC"))
    )
    (comp (ref "C32")
      (value "1uF")
      (footprint "easyedapro:C0603")
      (description "容值:1uF;精度:±10%;额定电压:50V;温度系数:X5R;")
      (fields
        (field (name "Manufacturer Part") "CL10A105KB8NNNC")
        (field (name "Manufacturer") "SAMSUNG(三星)")
      )
      (libsource (lib "easyedapro") (part "CL10A105KB8NNNC"))
    )
    (comp (ref "C33")
      (value "100nF")
      (footprint "easyedapro:C0603")
      (description "容值:100nF;精度:±10%;额定电压:50V;温度系数:X7R;")
      (fields
        (field (name "Manufacturer Part") "CC0603KRX7R9BB104")
        (field (name "Manufacturer") "YAGEO(国巨)")
      )
      (libsource (lib "easyedapro") (part "CC0603KRX7R9BB104"))
    )
    (comp (ref "C34")
      (value "100nF")
      (footprint "easyedapro:C0603")
      (description "容值:100nF;精度:±10%;额定电压:50V;温度系数:X7R;")
      (fields
        (field (name "Manufacturer Part") "CC0603KRX7R9BB104")
        (field (name "Manufacturer") "YAGEO(国巨)")
      )
      (libsource (lib "easyedapro") (part "CC0603KRX7R9BB104"))
    )
    (comp (ref "CN2")
      (value "~")
      (footprint "easyedapro:HDR-TH_10P-P2.54-V-M-R2-C5-S2.54")
      (fields
        (field (name "Manufacturer Part") "Z-21310110021001")
        (field (name "Manufacturer") "Nextron(台湾正凌)")
      )
      (libsource (lib "easyedapro") (part "Z-21310110021001"))
    )
    (comp (ref "D4")
      (value "SMF3.3A")
      (footprint "easyedapro:SOD-123_L2.8-W1.8-LS3.7-RD")
      (fields (field (name "Manufacturer") "DOWO"))
      (libsource (lib "easyedapro") (part "SMF3.3A"))
    )
    (comp (ref "D6")
      (value "LRB521S-40T1G")
      (footprint "easyedapro:SOD-523_L1.2-W0.8-LS1.6-RD")
      (description "直流反向耐压(Vr):40V;平均整流电流(Io):200mA;正向压降(Vf):300mV;")
      (fields (field (name "Manufacturer") "LRC(乐山无线电)"))
      (libsource (lib "easyedapro") (part "LRB521S-40T1G"))
    )
    (comp (ref "J8") (value "Header 1x4") (libsource (lib "easyedapro") (part "Header 1x4")))
    (comp (ref "JP2")
      (value "Header 1x3")
      (footprint "easyedapro:HEADER 1X3")
      (libsource (lib "easyedapro") (part "Header 1x3"))
    )
    (comp (ref "JP3") (value "NC(Header 1x2)") (libsource (lib "easyedapro") (part "NC(Header 1x2)")))
    (comp (ref "LED1") (value "RED") (libsource (lib "easyedapro") (part "RED(1)")))
    (comp (ref "LED2")
      (value "RED")
      (footprint "easyedapro:LED0603")
      (libsource (lib "easyedapro") (part "RED"))
    )
    (comp (ref "LED3")
      (value "YELLOW")
      (footprint "easyedapro:LED0603")
      (libsource (lib "easyedapro") (part "YELLOW"))
    )
    (comp (ref "LED4")
      (value "GREEN")
      (footprint "easyedapro:LED0603")
      (libsource (lib "easyedapro") (part "GREEN"))
    )
    (comp (ref "Q1")
      (value "SS8050")
      (footprint "easyedapro:SOT-23-3_L2.9-W1.3-P1.90-LS2.4-BR")
      (description "晶体管类型:-;集电极电流(Ic):-;集射极击穿电压(Vceo):-;功率(Pd):-;")
      (fields (field (name "Manufacturer") "JSMSEMI(杰盛微)"))
      (libsource (lib "easyedapro") (part "SS8050_C916392"))
    )
    (comp (ref "Q2")
      (value "SS8050")
      (footprint "easyedapro:SOT-23-3_L2.9-W1.3-P1.90-LS2.4-BR")
      (description "晶体管类型:-;集电极电流(Ic):-;集射极击穿电压(Vceo):-;功率(Pd):-;")
      (fields (field (name "Manufacturer") "JSMSEMI(杰盛微)"))
      (libsource (lib "easyedapro") (part "SS8050_C916392"))
    )
    (comp (ref "Q3")
      (value "SS8050")
      (footprint "easyedapro:SOT-23-3_L2.9-W1.3-P1.90-LS2.4-BR")
      (description "晶体管类型:-;集电极电流(Ic):-;集射极击穿电压(Vceo):-;功率(Pd):-;")
      (fields (field (name "Manufacturer") "JSMSEMI(杰盛微)"))
      (libsource (lib "easyedapro") (part "SS8050_C916392"))
    )
    (comp (ref "R3")
      (value "1kΩ")
      (footprint "easyedapro:R0603")
      (description "电阻类型:厚膜电阻;阻值:1kΩ;精度:±1%;功率:1/10W;温度系数:±100ppm/;最大工作电压:75V;工作温度范围:-55~+155;")
      (fields
        (field (name "Manufacturer Part") "0603WAF1001T5E")
        (field (name "Manufacturer") "UNI-ROYAL(厚声)")
      )
      (libsource (lib "easyedapro") (part "0603WAF1001T5E"))
    )
    (comp (ref "R5")
      (value "0Ω")
      (footprint "easyedapro:R0603")
      (description "电阻类型:厚膜电阻;阻值:0Ω;精度:±1%;功率:1/10W;温度系数:-;最大工作电压:75V;工作温度范围:-55~+155;")
      (fields
        (field (name "Manufacturer Part") "0603WAF0000T5E")
        (field (name "Manufacturer") "UNI-ROYAL(厚声)")
      )
      (libsource (lib "easyedapro") (part "0603WAF0000T5E"))
    )
    (comp (ref "R6") (value "NC") (footprint "easyedapro:SB-PAD") (libsource (lib "easyedapro") (part "NC")))
    (comp (ref "R7")
      (value "100kΩ")
      (footprint "easyedapro:R0603")
      (description "电阻类型:厚膜电阻;阻值:100kΩ;精度:±1%;功率:1/10W;温度系数:±100ppm/;最大工作电压:75V;工作温度范围:-55~+155;")
      (fields
        (field (name "Manufacturer Part") "0603WAF1003T5E")
        (field (name "Manufacturer") "UNI-ROYAL(厚声)")
      )
      (libsource (lib "easyedapro") (part "0603WAF1003T5E"))
    )
    (comp (ref "R9")
      (value "330Ω")
      (footprint "easyedapro:R0603")
      (description "阻值:100Ω;精度:±1%;功率:100mW;温度系数:±200ppm/°C;电阻类型:厚膜电阻;")
      (fields
        (field (name "Manufacturer Part") "0603WAF3300T5E")
        (field (name "Manufacturer") "UNI-ROYAL(厚声)")
      )
      (libsource (lib "easyedapro") (part "0603WAF1000T5E"))
    )
    (comp (ref "R10")
      (value "330Ω")
      (footprint "easyedapro:R0603")
      (description "阻值:100Ω;精度:±1%;功率:100mW;温度系数:±200ppm/°C;电阻类型:厚膜电阻;")
      (fields
        (field (name "Manufacturer Part") "0603WAF3300T5E")
        (field (name "Manufacturer") "UNI-ROYAL(厚声)")
      )
      (libsource (lib "easyedapro") (part "0603WAF1000T5E"))
    )
    (comp (ref "R13")
      (value "0Ω")
      (footprint "easyedapro:R0603")
      (description "电阻类型:厚膜电阻;阻值:0Ω;精度:±1%;功率:1/10W;温度系数:-;最大工作电压:75V;工作温度范围:-55~+155;")
      (fields
        (field (name "Manufacturer Part") "0603WAF0000T5E")
        (field (name "Manufacturer") "UNI-ROYAL(厚声)")
      )
      (libsource (lib "easyedapro") (part "0603WAF0000T5E"))
    )
    (comp (ref "R14")
      (value "1kΩ")
      (footprint "easyedapro:R0603")
      (description "电阻类型:厚膜电阻;阻值:1kΩ;精度:±1%;功率:1/10W;温度系数:±100ppm/;最大工作电压:75V;工作温度范围:-55~+155;")
      (fields
        (field (name "Manufacturer Part") "0603WAF1001T5E")
        (field (name "Manufacturer") "UNI-ROYAL(厚声)")
      )
      (libsource (lib "easyedapro") (part "0603WAF1001T5E"))
    )
    (comp (ref "R15")
      (value "1kΩ")
      (footprint "easyedapro:R0603")
      (description "电阻类型:厚膜电阻;阻值:1kΩ;精度:±1%;功率:1/10W;温度系数:±100ppm/;最大工作电压:75V;工作温度范围:-55~+155;")
      (fields
        (field (name "Manufacturer Part") "0603WAF1001T5E")
        (field (name "Manufacturer") "UNI-ROYAL(厚声)")
      )
      (libsource (lib "easyedapro") (part "0603WAF1001T5E"))
    )
    (comp (ref "R16")
      (value "1kΩ")
      (footprint "easyedapro:R0603")
      (description "电阻类型:厚膜电阻;阻值:1kΩ;精度:±1%;功率:1/10W;温度系数:±100ppm/;最大工作电压:75V;工作温度范围:-55~+155;")
      (fields
        (field (name "Manufacturer Part") "0603WAF1001T5E")
        (field (name "Manufacturer") "UNI-ROYAL(厚声)")
      )
      (libsource (lib "easyedapro") (part "0603WAF1001T5E"))
    )
    (comp (ref "R50")
      (value "47kΩ")
      (footprint "easyedapro:R0603")
      (description "电阻类型:厚膜电阻;阻值:47kΩ;精度:±1%;功率:1/10W;温度系数:±100ppm/;最大工作电压:75V;工作温度范围:-55~+155;")
      (fields
        (field (name "Manufacturer Part") "0603WAF4702T5E")
        (field (name "Manufacturer") "UNI-ROYAL(厚声)")
      )
      (libsource (lib "easyedapro") (part "0603WAF4702T5E"))
    )
    (comp (ref "R51")
      (value "15kΩ")
      (footprint "easyedapro:R0603")
      (description "电阻类型:厚膜电阻;阻值:15kΩ;精度:±1%;功率:1/10W;温度系数:±100ppm/;最大工作电压:75V;工作温度范围:-55~+155;")
      (fields
        (field (name "Manufacturer Part") "0603WAF1502T5E")
        (field (name "Manufacturer") "UNI-ROYAL(厚声)")
      )
      (libsource (lib "easyedapro") (part "0603WAF1502T5E"))
    )
    (comp (ref "R52")
      (value "100kΩ")
      (footprint "easyedapro:R0603")
      (description "电阻类型:厚膜电阻;阻值:100kΩ;精度:±1%;功率:1/10W;温度系数:±100ppm/;最大工作电压:75V;工作温度范围:-55~+155;")
      (fields
        (field (name "Manufacturer Part") "0603WAF1003T5E")
        (field (name "Manufacturer") "UNI-ROYAL(厚声)")
      )
      (libsource (lib "easyedapro") (part "0603WAF1003T5E"))
    )
    (comp (ref "R53")
      (value "10kΩ")
      (footprint "easyedapro:R0603")
      (description "电阻类型:厚膜电阻;阻值:10kΩ;精度:±1%;功率:1/10W;温度系数:±100ppm/;最大工作电压:75V;工作温度范围:-55~+155;")
      (fields
        (field (name "Manufacturer Part") "0603WAF1002T5E")
        (field (name "Manufacturer") "UNI-ROYAL(厚声)")
      )
      (libsource (lib "easyedapro") (part "0603WAF1002T5E"))
    )
    (comp (ref "R54")
      (value "10kΩ")
      (footprint "easyedapro:R0603")
      (description "电阻类型:厚膜电阻;阻值:10kΩ;精度:±1%;功率:1/10W;温度系数:±100ppm/;最大工作电压:75V;工作温度范围:-55~+155;")
      (fields
        (field (name "Manufacturer Part") "0603WAF1002T5E")
        (field (name "Manufacturer") "UNI-ROYAL(厚声)")
      )
      (libsource (lib "easyedapro") (part "0603WAF1002T5E"))
    )
    (comp (ref "R55")
      (value "100kΩ")
      (footprint "easyedapro:R0603")
      (description "电阻类型:厚膜电阻;阻值:100kΩ;精度:±1%;功率:1/10W;温度系数:±100ppm/;最大工作电压:75V;工作温度范围:-55~+155;")
      (fields
        (field (name "Manufacturer Part") "0603WAF1003T5E")
        (field (name "Manufacturer") "UNI-ROYAL(厚声)")
      )
      (libsource (lib "easyedapro") (part "0603WAF1003T5E"))
    )
    (comp (ref "R56")
      (value "100kΩ")
      (footprint "easyedapro:R0603")
      (description "电阻类型:厚膜电阻;阻值:100kΩ;精度:±1%;功率:1/10W;温度系数:±100ppm/;最大工作电压:75V;工作温度范围:-55~+155;")
      (fields
        (field (name "Manufacturer Part") "0603WAF1003T5E")
        (field (name "Manufacturer") "UNI-ROYAL(厚声)")
      )
      (libsource (lib "easyedapro") (part "0603WAF1003T5E"))
    )
    (comp (ref "R57")
      (value "10kΩ")
      (footprint "easyedapro:R0603")
      (description "电阻类型:厚膜电阻;阻值:10kΩ;精度:±1%;功率:1/10W;温度系数:±100ppm/;最大工作电压:75V;工作温度范围:-55~+155;")
      (fields
        (field (name "Manufacturer Part") "0603WAF1002T5E")
        (field (name "Manufacturer") "UNI-ROYAL(厚声)")
      )
      (libsource (lib "easyedapro") (part "0603WAF1002T5E"))
    )
    (comp (ref "T1")
      (value "Testpoint")
      (fields (field (name "Publisher") "Altium Limited"))
      (libsource (lib "easyedapro") (part "Testpoint"))
    )
    (comp (ref "T2")
      (value "Testpoint")
      (fields (field (name "Publisher") "Altium Limited"))
      (libsource (lib "easyedapro") (part "Testpoint"))
    )
    (comp (ref "U2")
      (value "RT9080N-08GJ5")
      (footprint "easyedapro:SOT-23-5")
      (libsource (lib "easyedapro") (part "RT9080N-08GJ5"))
    )
    (comp (ref "U3")
      (value "ME6211C18M5G-N")
      (footprint "easyedapro:SOT-23-5_L3.0-W1.7-P0.95-LS2.8-BR")
      (description "输出类型:固定;输出极性:正;最大输入电压:6.5V;输出电压:1.8V;输出电流:300mA;电源纹波抑制比(PSRR):70dB@(1kHz);")
      (fields (field (name "Manufacturer") "MICRONE(南京微盟)"))
      (libsource (lib "easyedapro") (part "ME6211C18M5G-N"))
    )
    (comp (ref "U4")
      (value "AIPTS0104TA14.TR")
      (footprint "easyedapro:TSSOP-14_L5.0-W4.4-P0.65-LS6.4-BL")
      (description "电路数:1;每个电路通道数:4;电压(VCCA):1.65V~5.5V;电压(VCCB):2.3V~5.5V;数据速率:24Mbps;")
      (fields (field (name "Manufacturer") "RUNIC(润石)"))
      (libsource (lib "easyedapro") (part "RS0104YQ"))
    )
    (comp (ref "J1")
      (value "~")
      (footprint "easyedapro:HDR-TH_24P-P2.54-V-M-R2-C12-S2.54")
      (fields (field (name "Manufacturer Part") "PZ254V-12-24P") (field (name "Manufacturer") "XFCN(台湾兴飞)"))
      (libsource (lib "easyedapro") (part "PZ254V-12-24P"))
    )
    (comp (ref "J2")
      (value "~")
      (footprint "easyedapro:HDR-TH_24P-P2.54-V-M-R2-C12-S2.54")
      (fields (field (name "Manufacturer Part") "PZ254V-12-24P") (field (name "Manufacturer") "XFCN(台湾兴飞)"))
      (libsource (lib "easyedapro") (part "PZ254V-12-24P"))
    )
    (comp (ref "J3")
      (value "~")
      (footprint "easyedapro:HDR-TH_10P-P2.54-V-F")
      (description "间距:2.54mm;总孔位数:10;排数:1;插孔结构:1x10P;行距:-;安装类型:直插;塑高:-;触头材质:-;触头镀层:-;")
      (fields (field (name "Manufacturer Part") "2.54-1*10P母") (field (name "Manufacturer") "BOOMELE(博穆精密)"))
      (libsource (lib "easyedapro") (part "Header-Female-2.54_1x10"))
    )
    (comp (ref "J4")
      (value "~")
      (footprint "easyedapro:HDR-TH_8P-P2.54-V-F-1")
      (description "间距:2.54mm;总孔位数:8;排数:1;插孔结构:1x8P;行距:-;安装类型:直插;塑高:-;触头材质:-;触头镀层:-;")
      (fields (field (name "Manufacturer Part") "2.54-1*8P母环保") (field (name "Manufacturer") "BOOMELE(博穆精密)"))
      (libsource (lib "easyedapro") (part "Header-Female-2.54_1x8"))
    )
    (comp (ref "J5")
      (value "~")
      (footprint "easyedapro:HDR-TH_8P-P2.54-V-F-1")
      (description "间距:2.54mm;总孔位数:8;排数:1;插孔结构:1x8P;行距:-;安装类型:直插;塑高:-;触头材质:-;触头镀层:-;")
      (fields (field (name "Manufacturer Part") "2.54-1*8P母环保") (field (name "Manufacturer") "BOOMELE(博穆精密)"))
      (libsource (lib "easyedapro") (part "Header-Female-2.54_1x8"))
    )
    (comp (ref "J6")
      (value "~")
      (footprint "easyedapro:HDR-TH_6P-P2.54-V-F")
      (description "间距:2.54mm;总孔位数:6;排数:1;插孔结构:1x6P;行距:-;安装类型:直插;塑高:-;触头材质:-;触头镀层:-;")
      (fields (field (name "Manufacturer Part") "2.54-1*6P母") (field (name "Manufacturer") "BOOMELE(博穆精密)"))
      (libsource (lib "easyedapro") (part "Header-Female-2.54_1x6"))
    )
    (comp (ref "J7")
      (value "Header 4X2")
      (fields (field (name "Publisher") "Altium Limited"))
      (libsource (lib "easyedapro") (part "Header 4X2"))
    )
    (comp (ref "R34")
      (value "0Ω")
      (footprint "easyedapro:R0603")
      (description "电阻类型:厚膜电阻;阻值:0Ω;精度:±1%;功率:1/10W;温度系数:-;最大工作电压:75V;工作温度范围:-55~+155;")
      (fields
        (field (name "Manufacturer Part") "0603WAF0000T5E")
        (field (name "Manufacturer") "UNI-ROYAL(厚声)")
      )
      (libsource (lib "easyedapro") (part "0603WAF0000T5E"))
    )
    (comp (ref "R35") (value "NC") (footprint "easyedapro:SB-PAD") (libsource (lib "easyedapro") (part "NC")))
    (comp (ref "R36") (value "NC") (footprint "easyedapro:SB-PAD") (libsource (lib "easyedapro") (part "NC")))
    (comp (ref "R37")
      (value "0Ω")
      (footprint "easyedapro:R0603")
      (description "电阻类型:厚膜电阻;阻值:0Ω;精度:±1%;功率:1/10W;温度系数:-;最大工作电压:75V;工作温度范围:-55~+155;")
      (fields
        (field (name "Manufacturer Part") "0603WAF0000T5E")
        (field (name "Manufacturer") "UNI-ROYAL(厚声)")
      )
      (libsource (lib "easyedapro") (part "0603WAF0000T5E"))
    )
    (comp (ref "R38") (value "NC") (footprint "easyedapro:SB-PAD") (libsource (lib "easyedapro") (part "NC")))
    (comp (ref "R39")
      (value "0Ω")
      (footprint "easyedapro:R0603")
      (description "电阻类型:厚膜电阻;阻值:0Ω;精度:±1%;功率:1/10W;温度系数:-;最大工作电压:75V;工作温度范围:-55~+155;")
      (fields
        (field (name "Manufacturer Part") "0603WAF0000T5E")
        (field (name "Manufacturer") "UNI-ROYAL(厚声)")
      )
      (libsource (lib "easyedapro") (part "0603WAF0000T5E"))
    )
  )
  (nets
    (net (code "1") (name "1V8") (class "Default")
      (node (ref "C32") (pin "2") (pinfunction "2_2") (pintype "input"))
      (node (ref "JP2") (pin "1") (pinfunction "1_1") (pintype "input"))
      (node (ref "U3") (pin "5") (pinfunction "VOUT_5") (pintype "input"))
    )
    (net (code "2") (name "3V3") (class "Default")
      (node (ref "C17") (pin "2") (pinfunction "2_2") (pintype "input"))
      (node (ref "C31") (pin "2") (pinfunction "2_2") (pintype "input"))
      (node (ref "C33") (pin "1") (pinfunction "1_1") (pintype "input"))
      (node (ref "CN2") (pin "1") (pinfunction "1_1") (pintype "input"))
      (node (ref "D4") (pin "1") (pinfunction "1_1") (pintype "input"))
      (node (ref "JP2") (pin "3") (pinfunction "3_3") (pintype "input"))
      (node (ref "R14") (pin "2") (pinfunction "2_2") (pintype "input"))
      (node (ref "R15") (pin "2") (pinfunction "2_2") (pintype "input"))
      (node (ref "R16") (pin "2") (pinfunction "2_2") (pintype "input"))
      (node (ref "R3") (pin "2") (pinfunction "2_2") (pintype "input"))
      (node (ref "R50") (pin "2") (pinfunction "2_2") (pintype "input"))
      (node (ref "U2") (pin "5") (pinfunction "OUT_5") (pintype "input"))
      (node (ref "U3") (pin "1") (pinfunction "VIN_1") (pintype "input"))
      (node (ref "U3") (pin "3") (pinfunction "CE_3") (pintype "input"))
      (node (ref "U4") (pin "14") (pinfunction "VCCB_14") (pintype "unspecified"))
    )
    (net (code "3") (name "ATLINK_5V") (class "Default")
      (node (ref "CN6") (pin "A4B9") (pinfunction "VBUS_A4B9") (pintype "input"))
      (node (ref "CN6") (pin "B4A9") (pinfunction "VBUS_B4A9") (pintype "input"))
      (node (ref "F2") (pin "1") (pinfunction "1_1") (pintype "input"))
      (node (ref "TP1") (pin "1") (pinfunction "1_1") (pintype "input"))
    )
    (net (code "4") (name "ATLK_NRST") (class "Default")
      (node (ref "CN2") (pin "7") (pinfunction "7_7") (pintype "input"))
      (node (ref "D6") (pin "1") (pinfunction "K_1") (pintype "unspecified"))
      (node (ref "RP2") (pin "4") (pinfunction "4_4") (pintype "input"))
    )
    (net (code "5") (name "ATLK_RX") (class "Default")
      (node (ref "CN2") (pin "10") (pinfunction "10_10") (pintype "input"))
      (node (ref "RP3") (pin "2") (pinfunction "2_2") (pintype "input"))
      (node (ref "U4") (pin "10") (pinfunction "B4_10") (pintype "unspecified"))
    )
    (net (code "6") (name "ATLK_SWCLK") (class "Default")
      (node (ref "CN2") (pin "5") (pinfunction "5_5") (pintype "input"))
      (node (ref "RP2") (pin "1") (pinfunction "1_1") (pintype "input"))
      (node (ref "U4") (pin "12") (pinfunction "B2_12") (pintype "unspecified"))
    )
    (net (code "7") (name "ATLK_SWDIO") (class "Default")
      (node (ref "CN2") (pin "3") (pinfunction "3_3") (pintype "input"))
      (node (ref "RP2") (pin "2") (pinfunction "2_2") (pintype "input"))
      (node (ref "U4") (pin "13") (pinfunction "B1_13") (pintype "unspecified"))
    )
    (net (code "8") (name "ATLK_TX") (class "Default")
      (node (ref "CN2") (pin "8") (pinfunction "8_8") (pintype "input"))
      (node (ref "RP3") (pin "1") (pinfunction "1_1") (pintype "input"))
      (node (ref "U4") (pin "11") (pinfunction "B3_11") (pintype "unspecified"))
    )
    (net (code "9") (name "BOOT0") (class "Default")
      (node (ref "J1") (pin "20") (pinfunction "20_20") (pintype "input"))
      (node (ref "R31") (pin "2") (pinfunction "2_2") (pintype "input"))
      (node (ref "U1") (pin "44") (pinfunction "BOOT0_44") (pintype "input"))
    )
    (net (code "10") (name "CC1") (class "Default")
      (node (ref "CN6") (pin "A5") (pinfunction "CC1_A5") (pintype "input"))
      (node (ref "R20") (pin "1") (pinfunction "1_1") (pintype "input"))
    )
    (net (code "11") (name "CC2") (class "Default")
      (node (ref "CN6") (pin "B5") (pinfunction "CC2_B5") (pintype "input"))
      (node (ref "R21") (pin "1") (pinfunction "1_1") (pintype "input"))
    )
    (net (code "12") (name "E5V") (class "Default")
      (node (ref "C18") (pin "2") (pinfunction "2_2") (pintype "input"))
      (node (ref "C19") (pin "2") (pinfunction "2_2") (pintype "input"))
      (node (ref "CN2") (pin "2") (pinfunction "2_2") (pintype "input"))
      (node (ref "D3") (pin "1") (pinfunction "1_1") (pintype "input"))
      (node (ref "J4") (pin "5") (pinfunction "5_5") (pintype "input"))
      (node (ref "J7") (pin "2") (pinfunction "2_2") (pintype "input"))
      (node (ref "U2") (pin "1") (pinfunction "IN_1") (pintype "input"))
      (node (ref "U2") (pin "3") (pinfunction "EN_3") (pintype "input"))
    )
    (net (code "13") (name "EGND") (class "Default")
      (node (ref "C30") (pin "2") (pinfunction "2_2") (pintype "input"))
      (node (ref "CN6") (pin "13") (pinfunction "GND_13") (pintype "input"))
      (node (ref "CN6") (pin "14") (pinfunction "GND_14") (pintype "input"))
      (node (ref "CN6") (pin "15") (pinfunction "GND_15") (pintype "input"))
      (node (ref "CN6") (pin "16") (pinfunction "GND_16") (pintype "input"))
      (node (ref "R4") (pin "1") (pinfunction "1_1") (pintype "input"))
    )
    (net (code "14") (name "GND") (class "Default")
      (node (ref "B1") (pin "3") (pinfunction "3_3") (pintype "input"))
      (node (ref "B1") (pin "4") (pinfunction "4_4") (pintype "input"))
      (node (ref "C10") (pin "1") (pinfunction "1_1") (pintype "input"))
      (node (ref "C11") (pin "1") (pinfunction "1_1") (pintype "input"))
      (node (ref "C12") (pin "1") (pinfunction "1_1") (pintype "input"))
      (node (ref "C13") (pin "1") (pinfunction "1_1") (pintype "input"))
      (node (ref "C14") (pin "1") (pinfunction "1_1") (pintype "input"))
      (node (ref "C15") (pin "1") (pinfunction "1_1") (pintype "input"))
      (node (ref "C16") (pin "1") (pinfunction "1_1") (pintype "input"))
      (node (ref "C17") (pin "1") (pinfunction "1_1") (pintype "input"))
      (node (ref "C18") (pin "1") (pinfunction "1_1") (pintype "input"))
      (node (ref "C19") (pin "1") (pinfunction "1_1") (pintype "input"))
      (node (ref "C22") (pin "1") (pinfunction "1_1") (pintype "input"))
      (node (ref "C23") (pin "1") (pinfunction "1_1") (pintype "input"))
      (node (ref "C24") (pin "1") (pinfunction "1_1") (pintype "input"))
      (node (ref "C25") (pin "1") (pinfunction "1_1") (pintype "input"))
      (node (ref "C26") (pin "1") (pinfunction "1_1") (pintype "input"))
      (node (ref "C27") (pin "1") (pinfunction "1_1") (pintype "input"))
      (node (ref "C28") (pin "1") (pinfunction "1_1") (pintype "input"))
      (node (ref "C30") (pin "1") (pinfunction "1_1") (pintype "input"))
      (node (ref "C31") (pin "1") (pinfunction "1_1") (pintype "input"))
      (node (ref "C32") (pin "1") (pinfunction "1_1") (pintype "input"))
      (node (ref "C33") (pin "2") (pinfunction "2_2") (pintype "input"))
      (node (ref "C34") (pin "1") (pinfunction "1_1") (pintype "input"))
      (node (ref "C4") (pin "1") (pinfunction "1_1") (pintype "input"))
      (node (ref "C5") (pin "1") (pinfunction "1_1") (pintype "input"))
      (node (ref "C6") (pin "1") (pinfunction "1_1") (pintype "input"))
      (node (ref "C7") (pin "1") (pinfunction "1_1") (pintype "input"))
      (node (ref "C8") (pin "1") (pinfunction "1_1") (pintype "input"))
      (node (ref "C9") (pin "1") (pinfunction "1_1") (pintype "input"))
      (node (ref "CN2") (pin "9") (pinfunction "9_9") (pintype "input"))
      (node (ref "CN6") (pin "A1B12") (pinfunction "GND_A1B12") (pintype "input"))
      (node (ref "CN6") (pin "B1A12") (pinfunction "GND_B1A12") (pintype "input"))
      (node (ref "D4") (pin "2") (pinfunction "2_2") (pintype "input"))
      (node (ref "J1") (pin "23") (pinfunction "23_23") (pintype "input"))
      (node (ref "J2") (pin "23") (pinfunction "23_23") (pintype "input"))
      (node (ref "J3") (pin "7") (pinfunction "7_7") (pintype "input"))
      (node (ref "J4") (pin "6") (pinfunction "6_6") (pintype "input"))
      (node (ref "J4") (pin "7") (pinfunction "7_7") (pintype "input"))
      (node (ref "J7") (pin "6") (pinfunction "6_6") (pintype "input"))
      (node (ref "J8") (pin "4") (pinfunction "4_4") (pintype "input"))
      (node (ref "JP1") (pin "3") (pinfunction "3_3") (pintype "input"))
      (node (ref "LED1") (pin "2") (pinfunction "CATHODE_2") (pintype "input"))
      (node (ref "P1") (pin "5") (pinfunction "5_5") (pintype "input"))
      (node (ref "Q1") (pin "2") (pinfunction "E_2") (pintype "input"))
      (node (ref "Q2") (pin "2") (pinfunction "E_2") (pintype "input"))
      (node (ref "Q3") (pin "2") (pinfunction "E_2") (pintype "input"))
      (node (ref "R20") (pin "2") (pinfunction "2_2") (pintype "input"))
      (node (ref "R21") (pin "2") (pinfunction "2_2") (pintype "input"))
      (node (ref "R4") (pin "2") (pinfunction "2_2") (pintype "input"))
      (node (ref "R49") (pin "1") (pinfunction "1_1") (pintype "input"))
      (node (ref "R51") (pin "1") (pinfunction "1_1") (pintype "input"))
      (node (ref "R52") (pin "1") (pinfunction "1_1") (pintype "input"))
      (node (ref "R55") (pin "1") (pinfunction "1_1") (pintype "input"))
      (node (ref "R56") (pin "1") (pinfunction "1_1") (pintype "input"))
      (node (ref "R7") (pin "1") (pinfunction "1_1") (pintype "input"))
      (node (ref "T1") (pin "1") (pinfunction "1_1") (pintype "input"))
      (node (ref "T2") (pin "1") (pinfunction "1_1") (pintype "input"))
      (node (ref "TP1") (pin "4") (pinfunction "4_4") (pintype "input"))
      (node (ref "U1") (pin "23") (pinfunction "VSS_23") (pintype "input"))
      (node (ref "U1") (pin "47") (pinfunction "VSS_47") (pintype "input"))
      (node (ref "U1") (pin "8") (pinfunction "VSSA_8") (pintype "input"))
      (node (ref "U2") (pin "2") (pinfunction "GND_2") (pintype "input"))
      (node (ref "U3") (pin "2") (pinfunction "VSS_2") (pintype "input"))
      (node (ref "U4") (pin "7") (pinfunction "GND_7") (pintype "unspecified"))
      (node (ref "U6") (pin "20") (pinfunction "PB2_20") (pintype "input"))
      (node (ref "U6") (pin "23") (pinfunction "VSS_1_23") (pintype "input"))
      (node (ref "U6") (pin "35") (pinfunction "VSS_2_35") (pintype "input"))
      (node (ref "U6") (pin "39") (pinfunction "PB3_39") (pintype "input"))
      (node (ref "U6") (pin "40") (pinfunction "PB4_40") (pintype "input"))
      (node (ref "U6") (pin "44") (pinfunction "BOOT0_44") (pintype "input"))
      (node (ref "U6") (pin "47") (pinfunction "VSS_3_47") (pintype "input"))
      (node (ref "U6") (pin "8") (pinfunction "VSSA_8") (pintype "input"))
      (node (ref "U7") (pin "2") (pinfunction "GND_2") (pintype "input"))
      (node (ref "Y2") (pin "2") (pinfunction "GND_2") (pintype "input"))
      (node (ref "Y2") (pin "4") (pinfunction "GND_4") (pintype "input"))
    )
    (net (code "15") (name "LD1") (class "Default")
      (node (ref "LD1") (pin "2") (pinfunction "CATHODE_2") (pintype "input"))
      (node (ref "U6") (pin "10") (pinfunction "PA0-WKUP_10") (pintype "input"))
    )
    (net (code "16") (name "LD2") (class "Default")
      (node (ref "LD2") (pin "2") (pinfunction "CATHODE_2") (pintype "input"))
      (node (ref "U6") (pin "11") (pinfunction "PA1_11") (pintype "input"))
    )
    (net (code "17") (name "LD3") (class "Default")
      (node (ref "LD3") (pin "2") (pinfunction "CATHODE_2") (pintype "input"))
      (node (ref "U6") (pin "12") (pinfunction "PA2_12") (pintype "input"))
    )
    (net (code "18") (name "LD4") (class "Default")
      (node (ref "LD4") (pin "2") (pinfunction "CATHODE_2") (pintype "input"))
      (node (ref "U6") (pin "19") (pinfunction "PB1_19") (pintype "input"))
    )
    (net (code "19") (name "M-ATLK_RX") (class "Default")
      (node (ref "RP3") (pin "7") (pinfunction "7_7") (pintype "input"))
      (node (ref "U6") (pin "31") (pinfunction "PA10_31") (pintype "input"))
    )
    (net (code "20") (name "M-ATLK_TX") (class "Default")
      (node (ref "RP3") (pin "8") (pinfunction "8_8") (pintype "input"))
      (node (ref "U6") (pin "30") (pinfunction "PA9_30") (pintype "input"))
    )
    (net (code "21") (name "M-NRST") (class "Default")
      (node (ref "C22") (pin "2") (pinfunction "2_2") (pintype "input"))
      (node (ref "P1") (pin "4") (pinfunction "4_4") (pintype "input"))
      (node (ref "U6") (pin "7") (pinfunction "NRST_7") (pintype "input"))
    )
    (net (code "22") (name "M-SWCLK") (class "Default")
      (node (ref "P1") (pin "3") (pinfunction "3_3") (pintype "input"))
      (node (ref "U6") (pin "37") (pinfunction "PA14_37") (pintype "input"))
    )
    (net (code "23") (name "M-SWDIO") (class "Default")
      (node (ref "P1") (pin "2") (pinfunction "2_2") (pintype "input"))
      (node (ref "U6") (pin "34") (pinfunction "PA13_34") (pintype "input"))
    )
    (net (code "24") (name "M-USB_D+") (class "Default")
      (node (ref "R11") (pin "2") (pinfunction "2_2") (pintype "input"))
      (node (ref "U6") (pin "33") (pinfunction "PA12_33") (pintype "input"))
    )
    (net (code "25") (name "M-USB_D-") (class "Default")
      (node (ref "R12") (pin "2") (pinfunction "2_2") (pintype "input"))
      (node (ref "U6") (pin "32") (pinfunction "PA11_32") (pintype "input"))
    )
    (net (code "26") (name "M_ATLK_BOOT0") (class "Default")
      (node (ref "RP2") (pin "6") (pinfunction "6_6") (pintype "input"))
      (node (ref "U6") (pin "27") (pinfunction "PB14_27") (pintype "input"))
    )
    (net (code "27") (name "M_ATLK_NRST") (class "Default")
      (node (ref "RP2") (pin "5") (pinfunction "5_5") (pintype "input"))
      (node (ref "U6") (pin "28") (pinfunction "PB15_28") (pintype "input"))
    )
    (net (code "28") (name "M_ATLK_SWCLK") (class "Default")
      (node (ref "RP2") (pin "8") (pinfunction "8_8") (pintype "input"))
      (node (ref "U6") (pin "25") (pinfunction "PB12_25") (pintype "input"))
    )
    (net (code "29") (name "M_ATLK_SWDIO") (class "Default")
      (node (ref "RP2") (pin "7") (pinfunction "7_7") (pintype "input"))
      (node (ref "U6") (pin "26") (pinfunction "PB13_26") (pintype "input"))
    )
    (net (code "30") (name "M_ATLK_SWO") (class "Default")
      (node (ref "RP3") (pin "6") (pinfunction "6_6") (pintype "input"))
      (node (ref "U6") (pin "13") (pinfunction "PA3_13") (pintype "input"))
    )
    (net (code "31") (name "NRST") (class "Default")
      (node (ref "B1") (pin "1") (pinfunction "1_1") (pintype "input"))
      (node (ref "B1") (pin "2") (pinfunction "2_2") (pintype "input"))
      (node (ref "C13") (pin "2") (pinfunction "2_2") (pintype "input"))
      (node (ref "D6") (pin "2") (pinfunction "A_2") (pintype "unspecified"))
      (node (ref "J2") (pin "7") (pinfunction "7_7") (pintype "input"))
      (node (ref "J4") (pin "3") (pinfunction "3_3") (pintype "input"))
      (node (ref "J7") (pin "5") (pinfunction "5_5") (pintype "input"))
      (node (ref "U1") (pin "7") (pinfunction "NRST_7") (pintype "input"))
    )
    (net (code "32") (name "Net-(B2-Pad3)") (class "Default")
      (node (ref "B2") (pin "3") (pinfunction "3_3") (pintype "input"))
      (node (ref "B2") (pin "4") (pinfunction "4_4") (pintype "input"))
      (node (ref "R5") (pin "1") (pinfunction "1_1") (pintype "input"))
      (node (ref "R6") (pin "1") (pinfunction "1_1") (pintype "input"))
      (node (ref "R7") (pin "2") (pinfunction "2_2") (pintype "input"))
    )
    (net (code "33") (name "Net-(C23-Pad2)") (class "Default")
      (node (ref "C23") (pin "2") (pinfunction "2_2") (pintype "input"))
      (node (ref "R22") (pin "1") (pinfunction "1_1") (pintype "input"))
      (node (ref "Y1") (pin "1") (pinfunction "1_1") (pintype "input"))
    )
    (net (code "34") (name "Net-(C24-Pad2)") (class "Default")
      (node (ref "C24") (pin "2") (pinfunction "2_2") (pintype "input"))
      (node (ref "R23") (pin "1") (pinfunction "1_1") (pintype "input"))
      (node (ref "Y1") (pin "2") (pinfunction "2_2") (pintype "input"))
    )
    (net (code "35") (name "Net-(J3-Pad3)") (class "Default")
      (node (ref "J3") (pin "3") (pinfunction "3_3") (pintype "input"))
      (node (ref "R38") (pin "1") (pinfunction "1_1") (pintype "input"))
      (node (ref "R39") (pin "2") (pinfunction "2_2") (pintype "input"))
    )
    (net (code "36") (name "Net-(J6-Pad5)") (class "Default")
      (node (ref "J6") (pin "5") (pinfunction "5_5") (pintype "input"))
      (node (ref "R34") (pin "2") (pinfunction "2_2") (pintype "input"))
      (node (ref "R35") (pin "2") (pinfunction "2_2") (pintype "input"))
    )
    (net (code "37") (name "Net-(J6-Pad6)") (class "Default")
      (node (ref "J6") (pin "6") (pinfunction "6_6") (pintype "input"))
      (node (ref "R36") (pin "2") (pinfunction "2_2") (pintype "input"))
      (node (ref "R37") (pin "2") (pinfunction "2_2") (pintype "input"))
    )
    (net (code "38") (name "Net-(JP1-Pad2)") (class "Default")
      (node (ref "JP1") (pin "2") (pinfunction "2_2") (pintype "input"))
      (node (ref "R31") (pin "1") (pinfunction "1_1") (pintype "input"))
    )
    (net (code "39") (name "Net-(LD1-ANODE)") (class "Default")
      (node (ref "LD1") (pin "1") (pinfunction "ANODE_1") (pintype "input"))
      (node (ref "RP1") (pin "8") (pinfunction "8_8") (pintype "input"))
    )
    (net (code "40") (name "Net-(LD2-ANODE)") (class "Default")
      (node (ref "LD2") (pin "1") (pinfunction "ANODE_1") (pintype "input"))
      (node (ref "RP1") (pin "7") (pinfunction "7_7") (pintype "input"))
    )
    (net (code "41") (name "Net-(LD3-ANODE)") (class "Default")
      (node (ref "LD3") (pin "1") (pinfunction "ANODE_1") (pintype "input"))
      (node (ref "RP1") (pin "6") (pinfunction "6_6") (pintype "input"))
    )
    (net (code "42") (name "Net-(LD4-ANODE)") (class "Default")
      (node (ref "LD4") (pin "1") (pinfunction "ANODE_1") (pintype "input"))
      (node (ref "RP1") (pin "5") (pinfunction "5_5") (pintype "input"))
    )
    (net (code "43") (name "Net-(LED1-ANODE)") (class "Default")
      (node (ref "LED1") (pin "1") (pinfunction "ANODE_1") (pintype "input"))
      (node (ref "R3") (pin "1") (pinfunction "1_1") (pintype "input"))
    )
    (net (code "44") (name "Net-(LED2-ANODE)") (class "Default")
      (node (ref "LED2") (pin "1") (pinfunction "ANODE_1") (pintype "input"))
      (node (ref "R14") (pin "1") (pinfunction "1_1") (pintype "input"))
    )
    (net (code "45") (name "Net-(LED2-CATHODE)") (class "Default")
      (node (ref "LED2") (pin "2") (pinfunction "CATHODE_2") (pintype "input"))
      (node (ref "Q1") (pin "3") (pinfunction "C_3") (pintype "input"))
    )
    (net (code "46") (name "Net-(LED3-ANODE)") (class "Default")
      (node (ref "LED3") (pin "1") (pinfunction "ANODE_1") (pintype "input"))
      (node (ref "R15") (pin "1") (pinfunction "1_1") (pintype "input"))
    )
    (net (code "47") (name "Net-(LED3-CATHODE)") (class "Default")
      (node (ref "LED3") (pin "2") (pinfunction "CATHODE_2") (pintype "input"))
      (node (ref "Q2") (pin "3") (pinfunction "C_3") (pintype "input"))
    )
    (net (code "48") (name "Net-(LED4-ANODE)") (class "Default")
      (node (ref "LED4") (pin "1") (pinfunction "ANODE_1") (pintype "input"))
      (node (ref "R16") (pin "1") (pinfunction "1_1") (pintype "input"))
    )
    (net (code "49") (name "Net-(LED4-CATHODE)") (class "Default")
      (node (ref "LED4") (pin "2") (pinfunction "CATHODE_2") (pintype "input"))
      (node (ref "Q3") (pin "3") (pinfunction "C_3") (pintype "input"))
    )
    (net (code "50") (name "Net-(Q1-B)") (class "Default")
      (node (ref "Q1") (pin "1") (pinfunction "B_1") (pintype "input"))
      (node (ref "R52") (pin "2") (pinfunction "2_2") (pintype "input"))
      (node (ref "R53") (pin "2") (pinfunction "2_2") (pintype "input"))
    )
    (net (code "51") (name "Net-(Q2-B)") (class "Default")
      (node (ref "Q2") (pin "1") (pinfunction "B_1") (pintype "input"))
      (node (ref "R54") (pin "2") (pinfunction "2_2") (pintype "input"))
      (node (ref "R55") (pin "2") (pinfunction "2_2") (pintype "input"))
    )
    (net (code "52") (name "Net-(Q3-B)") (class "Default")
      (node (ref "Q3") (pin "1") (pinfunction "B_1") (pintype "input"))
      (node (ref "R56") (pin "2") (pinfunction "2_2") (pintype "input"))
      (node (ref "R57") (pin "2") (pinfunction "2_2") (pintype "input"))
    )
    (net (code "53") (name "Net-(U2-SNS)") (class "Default")
      (node (ref "R50") (pin "1") (pinfunction "1_1") (pintype "input"))
      (node (ref "R51") (pin "2") (pinfunction "2_2") (pintype "input"))
      (node (ref "U2") (pin "4") (pinfunction "SNS_4") (pintype "input"))
    )
    (net (code "54") (name "Net-(U4-A3)") (class "Default")
      (node (ref "R9") (pin "1") (pinfunction "1_1") (pintype "input"))
      (node (ref "U4") (pin "4") (pinfunction "A3_4") (pintype "unspecified"))
    )
    (net (code "55") (name "Net-(U4-A4)") (class "Default")
      (node (ref "R10") (pin "1") (pinfunction "1_1") (pintype "input"))
      (node (ref "U4") (pin "5") (pinfunction "A4_5") (pintype "unspecified"))
    )
    (net (code "56") (name "Net-(U7-EN)") (class "Default")
      (node (ref "C15") (pin "2") (pinfunction "2_2") (pintype "input"))
      (node (ref "C16") (pin "2") (pinfunction "2_2") (pintype "input"))
      (node (ref "D3") (pin "2") (pinfunction "2_2") (pintype "input"))
      (node (ref "F2") (pin "2") (pinfunction "2_2") (pintype "input"))
      (node (ref "U7") (pin "1") (pinfunction "IN_1") (pintype "input"))
      (node (ref "U7") (pin "3") (pinfunction "EN_3") (pintype "input"))
    )
    (net (code "57") (name "Net-(U7-SNS)") (class "Default")
      (node (ref "R43") (pin "1") (pinfunction "1_1") (pintype "input"))
      (node (ref "R49") (pin "2") (pinfunction "2_2") (pintype "input"))
      (node (ref "U7") (pin "4") (pinfunction "SNS_4") (pintype "input"))
    )
    (net (code "58") (name "Net-(Y2-OSC1)") (class "Default")
      (node (ref "C25") (pin "2") (pinfunction "2_2") (pintype "input"))
      (node (ref "R26") (pin "1") (pinfunction "1_1") (pintype "input"))
      (node (ref "Y2") (pin "1") (pinfunction "OSC1_1") (pintype "input"))
    )
    (net (code "59") (name "Net-(Y2-OSC2)") (class "Default")
      (node (ref "C26") (pin "2") (pinfunction "2_2") (pintype "input"))
      (node (ref "R27") (pin "1") (pinfunction "1_1") (pintype "input"))
      (node (ref "Y2") (pin "3") (pinfunction "OSC2_3") (pintype "input"))
    )
    (net (code "60") (name "PA0") (class "Default")
      (node (ref "J2") (pin "10") (pinfunction "10_10") (pintype "input"))
      (node (ref "J6") (pin "1") (pinfunction "1_1") (pintype "input"))
      (node (ref "R5") (pin "2") (pinfunction "2_2") (pintype "input"))
      (node (ref "U1") (pin "10") (pinfunction "PA0_10") (pintype "input"))
    )
    (net (code "61") (name "PA1") (class "Default")
      (node (ref "J2") (pin "11") (pinfunction "11_11") (pintype "input"))
      (node (ref "J6") (pin "2") (pinfunction "2_2") (pintype "input"))
      (node (ref "U1") (pin "11") (pinfunction "PA1_11") (pintype "input"))
    )
    (net (code "62") (name "PA2") (class "Default")
      (node (ref "J2") (pin "12") (pinfunction "12_12") (pintype "input"))
      (node (ref "J5") (pin "2") (pinfunction "2_2") (pintype "input"))
      (node (ref "U1") (pin "12") (pinfunction "PA2_12") (pintype "input"))
    )
    (net (code "63") (name "PA3") (class "Default")
      (node (ref "J2") (pin "13") (pinfunction "13_13") (pintype "input"))
      (node (ref "J5") (pin "1") (pinfunction "1_1") (pintype "input"))
      (node (ref "U1") (pin "13") (pinfunction "PA3_13") (pintype "input"))
    )
    (net (code "64") (name "PA4") (class "Default")
      (node (ref "J2") (pin "14") (pinfunction "14_14") (pintype "input"))
      (node (ref "J6") (pin "3") (pinfunction "3_3") (pintype "input"))
      (node (ref "U1") (pin "14") (pinfunction "PA4_14") (pintype "input"))
    )
    (net (code "65") (name "PA5") (class "Default")
      (node (ref "J2") (pin "15") (pinfunction "15_15") (pintype "input"))
      (node (ref "J3") (pin "6") (pinfunction "6_6") (pintype "input"))
      (node (ref "U1") (pin "15") (pinfunction "PA5_15") (pintype "input"))
    )
    (net (code "66") (name "PA6") (class "Default")
      (node (ref "J2") (pin "16") (pinfunction "16_16") (pintype "input"))
      (node (ref "J3") (pin "5") (pinfunction "5_5") (pintype "input"))
      (node (ref "R34") (pin "1") (pinfunction "1_1") (pintype "input"))
      (node (ref "U1") (pin "16") (pinfunction "PA6_16") (pintype "input"))
    )
    (net (code "67") (name "PA7") (class "Default")
      (node (ref "J2") (pin "17") (pinfunction "17_17") (pintype "input"))
      (node (ref "J3") (pin "4") (pinfunction "4_4") (pintype "input"))
      (node (ref "U1") (pin "17") (pinfunction "PA7_17") (pintype "input"))
    )
    (net (code "68") (name "PA8") (class "Default")
      (node (ref "J1") (pin "5") (pinfunction "5_5") (pintype "input"))
      (node (ref "J5") (pin "7") (pinfunction "7_7") (pintype "input"))
      (node (ref "U1") (pin "29") (pinfunction "PA8_29") (pintype "input"))
    )
    (net (code "69") (name "PA9") (class "Default")
      (node (ref "J1") (pin "6") (pinfunction "6_6") (pintype "input"))
      (node (ref "J3") (pin "1") (pinfunction "1_1") (pintype "input"))
      (node (ref "J8") (pin "2") (pinfunction "2_2") (pintype "input"))
      (node (ref "R10") (pin "2") (pinfunction "2_2") (pintype "input"))
      (node (ref "U1") (pin "30") (pinfunction "PA9_30") (pintype "input"))
    )
    (net (code "70") (name "PA10") (class "Default")
      (node (ref "J1") (pin "7") (pinfunction "7_7") (pintype "input"))
      (node (ref "J5") (pin "3") (pinfunction "3_3") (pintype "input"))
      (node (ref "J8") (pin "3") (pinfunction "3_3") (pintype "input"))
      (node (ref "R9") (pin "2") (pinfunction "2_2") (pintype "input"))
      (node (ref "U1") (pin "31") (pinfunction "PA10_31") (pintype "input"))
    )
    (net (code "71") (name "PA11") (class "Default")
      (node (ref "J1") (pin "8") (pinfunction "8_8") (pintype "input"))
      (node (ref "U1") (pin "32") (pinfunction "PA11_32") (pintype "input"))
    )
    (net (code "72") (name "PA12") (class "Default")
      (node (ref "J1") (pin "9") (pinfunction "9_9") (pintype "input"))
      (node (ref "U1") (pin "33") (pinfunction "PA12_33") (pintype "input"))
    )
    (net (code "73") (name "PA13{slash}SWDIO") (class "Default")
      (node (ref "J1") (pin "10") (pinfunction "10_10") (pintype "input"))
      (node (ref "U1") (pin "34") (pinfunction "PA13_34") (pintype "input"))
      (node (ref "U4") (pin "2") (pinfunction "A1_2") (pintype "unspecified"))
    )
    (net (code "74") (name "PA14{slash}SWCLK") (class "Default")
      (node (ref "J1") (pin "13") (pinfunction "13_13") (pintype "input"))
      (node (ref "U1") (pin "37") (pinfunction "PA14_37") (pintype "input"))
      (node (ref "U4") (pin "3") (pinfunction "A2_3") (pintype "unspecified"))
    )
    (net (code "75") (name "PA15") (class "Default")
      (node (ref "J1") (pin "14") (pinfunction "14_14") (pintype "input"))
      (node (ref "R39") (pin "1") (pinfunction "1_1") (pintype "input"))
      (node (ref "U1") (pin "38") (pinfunction "PA15_38") (pintype "input"))
    )
    (net (code "76") (name "PB0") (class "Default")
      (node (ref "J2") (pin "18") (pinfunction "18_18") (pintype "input"))
      (node (ref "J6") (pin "4") (pinfunction "4_4") (pintype "input"))
      (node (ref "U1") (pin "18") (pinfunction "PB0_18") (pintype "input"))
    )
    (net (code "77") (name "PB1") (class "Default")
      (node (ref "J2") (pin "19") (pinfunction "19_19") (pintype "input"))
      (node (ref "R37") (pin "1") (pinfunction "1_1") (pintype "input"))
      (node (ref "U1") (pin "19") (pinfunction "PB1_19") (pintype "input"))
    )
    (net (code "78") (name "PB2") (class "Default")
      (node (ref "J2") (pin "20") (pinfunction "20_20") (pintype "input"))
      (node (ref "U1") (pin "20") (pinfunction "PB2_20") (pintype "input"))
    )
    (net (code "79") (name "PB3") (class "Default")
      (node (ref "J1") (pin "15") (pinfunction "15_15") (pintype "input"))
      (node (ref "J5") (pin "5") (pinfunction "5_5") (pintype "input"))
      (node (ref "U1") (pin "39") (pinfunction "PB3_39") (pintype "input"))
    )
    (net (code "80") (name "PB4") (class "Default")
      (node (ref "J1") (pin "16") (pinfunction "16_16") (pintype "input"))
      (node (ref "J5") (pin "6") (pinfunction "6_6") (pintype "input"))
      (node (ref "U1") (pin "40") (pinfunction "PB4_40") (pintype "input"))
    )
    (net (code "81") (name "PB5") (class "Default")
      (node (ref "J1") (pin "17") (pinfunction "17_17") (pintype "input"))
      (node (ref "J5") (pin "4") (pinfunction "4_4") (pintype "input"))
      (node (ref "U1") (pin "41") (pinfunction "PB5_41") (pintype "input"))
    )
    (net (code "82") (name "PB6") (class "Default")
      (node (ref "J1") (pin "18") (pinfunction "18_18") (pintype "input"))
      (node (ref "R38") (pin "2") (pinfunction "2_2") (pintype "input"))
      (node (ref "U1") (pin "42") (pinfunction "PB6_42") (pintype "input"))
    )
    (net (code "83") (name "PB7") (class "Default")
      (node (ref "J1") (pin "19") (pinfunction "19_19") (pintype "input"))
      (node (ref "J3") (pin "2") (pinfunction "2_2") (pintype "input"))
      (node (ref "U1") (pin "43") (pinfunction "PB7_43") (pintype "input"))
    )
    (net (code "84") (name "PB8") (class "Default")
      (node (ref "J1") (pin "21") (pinfunction "21_21") (pintype "input"))
      (node (ref "J3") (pin "10") (pinfunction "10_10") (pintype "input"))
      (node (ref "R36") (pin "1") (pinfunction "1_1") (pintype "input"))
      (node (ref "U1") (pin "45") (pinfunction "PB8_45") (pintype "input"))
    )
    (net (code "85") (name "PB9") (class "Default")
      (node (ref "J1") (pin "22") (pinfunction "22_22") (pintype "input"))
      (node (ref "J3") (pin "9") (pinfunction "9_9") (pintype "input"))
      (node (ref "R35") (pin "1") (pinfunction "1_1") (pintype "input"))
      (node (ref "U1") (pin "46") (pinfunction "PB9_46") (pintype "input"))
    )
    (net (code "86") (name "PB10") (class "Default")
      (node (ref "J2") (pin "21") (pinfunction "21_21") (pintype "input"))
      (node (ref "J5") (pin "8") (pinfunction "8_8") (pintype "input"))
      (node (ref "U1") (pin "21") (pinfunction "PB10_21") (pintype "input"))
    )
    (net (code "87") (name "PB11") (class "Default")
      (node (ref "J2") (pin "22") (pinfunction "22_22") (pintype "input"))
      (node (ref "J7") (pin "8") (pinfunction "8_8") (pintype "input"))
      (node (ref "R57") (pin "1") (pinfunction "1_1") (pintype "input"))
      (node (ref "U1") (pin "22") (pinfunction "PB11_22") (pintype "input"))
    )
    (net (code "88") (name "PB12") (class "Default")
      (node (ref "J1") (pin "1") (pinfunction "1_1") (pintype "input"))
      (node (ref "J7") (pin "7") (pinfunction "7_7") (pintype "input"))
      (node (ref "U1") (pin "25") (pinfunction "PB12_25") (pintype "input"))
    )
    (net (code "89") (name "PB13") (class "Default")
      (node (ref "J1") (pin "2") (pinfunction "2_2") (pintype "input"))
      (node (ref "J7") (pin "3") (pinfunction "3_3") (pintype "input"))
      (node (ref "U1") (pin "26") (pinfunction "PB13_26") (pintype "input"))
    )
    (net (code "90") (name "PB14") (class "Default")
      (node (ref "J1") (pin "3") (pinfunction "3_3") (pintype "input"))
      (node (ref "J7") (pin "1") (pinfunction "1_1") (pintype "input"))
      (node (ref "U1") (pin "27") (pinfunction "PB14_27") (pintype "input"))
    )
    (net (code "91") (name "PB15") (class "Default")
      (node (ref "J1") (pin "4") (pinfunction "4_4") (pintype "input"))
      (node (ref "J7") (pin "4") (pinfunction "4_4") (pintype "input"))
      (node (ref "U1") (pin "28") (pinfunction "PB15_28") (pintype "input"))
    )
    (net (code "92") (name "PC13") (class "Default")
      (node (ref "J2") (pin "2") (pinfunction "2_2") (pintype "input"))
      (node (ref "R6") (pin "2") (pinfunction "2_2") (pintype "input"))
      (node (ref "U1") (pin "2") (pinfunction "PC13_2") (pintype "input"))
    )
    (net (code "93") (name "PC14") (class "Default")
      (node (ref "J2") (pin "3") (pinfunction "3_3") (pintype "input"))
      (node (ref "R24") (pin "2") (pinfunction "2_2") (pintype "input"))
    )
    (net (code "94") (name "PC14{slash}LEXT_IN") (class "Default")
      (node (ref "R22") (pin "2") (pinfunction "2_2") (pintype "input"))
      (node (ref "R24") (pin "1") (pinfunction "1_1") (pintype "input"))
      (node (ref "U1") (pin "3") (pinfunction "PC14_3") (pintype "input"))
    )
    (net (code "95") (name "PC15") (class "Default")
      (node (ref "J2") (pin "4") (pinfunction "4_4") (pintype "input"))
      (node (ref "R25") (pin "2") (pinfunction "2_2") (pintype "input"))
    )
    (net (code "96") (name "PC15{slash}LEXT_OUT") (class "Default")
      (node (ref "R23") (pin "2") (pinfunction "2_2") (pintype "input"))
      (node (ref "R25") (pin "1") (pinfunction "1_1") (pintype "input"))
      (node (ref "U1") (pin "4") (pinfunction "PC15_4") (pintype "input"))
    )
    (net (code "97") (name "PF0") (class "Default")
      (node (ref "J2") (pin "5") (pinfunction "5_5") (pintype "input"))
      (node (ref "R28") (pin "2") (pinfunction "2_2") (pintype "input"))
    )
    (net (code "98") (name "PF0{slash}HEXT_IN") (class "Default")
      (node (ref "R26") (pin "2") (pinfunction "2_2") (pintype "input"))
      (node (ref "R28") (pin "1") (pinfunction "1_1") (pintype "input"))
      (node (ref "U1") (pin "5") (pinfunction "PF0_5") (pintype "input"))
    )
    (net (code "99") (name "PF1") (class "Default")
      (node (ref "J2") (pin "6") (pinfunction "6_6") (pintype "input"))
      (node (ref "R29") (pin "2") (pinfunction "2_2") (pintype "input"))
    )
    (net (code "100") (name "PF1{slash}HEXT_OUT") (class "Default")
      (node (ref "R27") (pin "2") (pinfunction "2_2") (pintype "input"))
      (node (ref "R29") (pin "1") (pinfunction "1_1") (pintype "input"))
      (node (ref "U1") (pin "6") (pinfunction "PF1_6") (pintype "input"))
    )
    (net (code "101") (name "PF6") (class "Default")
      (node (ref "J1") (pin "11") (pinfunction "11_11") (pintype "input"))
      (node (ref "R53") (pin "1") (pinfunction "1_1") (pintype "input"))
      (node (ref "U1") (pin "35") (pinfunction "PF6_35") (pintype "input"))
    )
    (net (code "102") (name "PF7") (class "Default")
      (node (ref "J1") (pin "12") (pinfunction "12_12") (pintype "input"))
      (node (ref "R54") (pin "1") (pinfunction "1_1") (pintype "input"))
      (node (ref "U1") (pin "36") (pinfunction "PF7_36") (pintype "input"))
    )
    (net (code "103") (name "USB+") (class "Default")
      (node (ref "CN6") (pin "A6") (pinfunction "DP1_A6") (pintype "input"))
      (node (ref "CN6") (pin "B6") (pinfunction "DP2_B6") (pintype "input"))
      (node (ref "R11") (pin "1") (pinfunction "1_1") (pintype "input"))
      (node (ref "TP1") (pin "3") (pinfunction "3_3") (pintype "input"))
    )
    (net (code "104") (name "USB-") (class "Default")
      (node (ref "CN6") (pin "A7") (pinfunction "DN1_A7") (pintype "input"))
      (node (ref "CN6") (pin "B7") (pinfunction "DN2_B7") (pintype "input"))
      (node (ref "R12") (pin "1") (pinfunction "1_1") (pintype "input"))
      (node (ref "TP1") (pin "2") (pinfunction "2_2") (pintype "input"))
    )
    (net (code "105") (name "VCC") (class "Default")
      (node (ref "C10") (pin "2") (pinfunction "2_2") (pintype "input"))
      (node (ref "C11") (pin "2") (pinfunction "2_2") (pintype "input"))
      (node (ref "C12") (pin "2") (pinfunction "2_2") (pintype "input"))
      (node (ref "C14") (pin "2") (pinfunction "2_2") (pintype "input"))
      (node (ref "C8") (pin "2") (pinfunction "2_2") (pintype "input"))
      (node (ref "C9") (pin "2") (pinfunction "2_2") (pintype "input"))
      (node (ref "P1") (pin "1") (pinfunction "1_1") (pintype "input"))
      (node (ref "R43") (pin "2") (pinfunction "2_2") (pintype "input"))
      (node (ref "RP1") (pin "1") (pinfunction "1_1") (pintype "input"))
      (node (ref "RP1") (pin "2") (pinfunction "2_2") (pintype "input"))
      (node (ref "RP1") (pin "3") (pinfunction "3_3") (pintype "input"))
      (node (ref "RP1") (pin "4") (pinfunction "4_4") (pintype "input"))
      (node (ref "U6") (pin "1") (pinfunction "VBAT_1") (pintype "input"))
      (node (ref "U6") (pin "24") (pinfunction "VDD_1_24") (pintype "input"))
      (node (ref "U6") (pin "36") (pinfunction "VDD_2_36") (pintype "input"))
      (node (ref "U6") (pin "48") (pinfunction "VDD_3_48") (pintype "input"))
      (node (ref "U6") (pin "9") (pinfunction "VDDA_9") (pintype "input"))
      (node (ref "U7") (pin "5") (pinfunction "OUT_5") (pintype "input"))
    )
    (net (code "106") (name "VDD") (class "Default")
      (node (ref "B2") (pin "1") (pinfunction "1_1") (pintype "input"))
      (node (ref "B2") (pin "2") (pinfunction "2_2") (pintype "input"))
      (node (ref "C4") (pin "2") (pinfunction "2_2") (pintype "input"))
      (node (ref "C5") (pin "2") (pinfunction "2_2") (pintype "input"))
      (node (ref "C6") (pin "2") (pinfunction "2_2") (pintype "input"))
      (node (ref "C7") (pin "2") (pinfunction "2_2") (pintype "input"))
      (node (ref "J1") (pin "24") (pinfunction "24_24") (pintype "input"))
      (node (ref "J2") (pin "1") (pinfunction "1_1") (pintype "input"))
      (node (ref "J2") (pin "24") (pinfunction "24_24") (pintype "input"))
      (node (ref "JP1") (pin "1") (pinfunction "1_1") (pintype "input"))
      (node (ref "JP3") (pin "2") (pinfunction "2_2") (pintype "input"))
      (node (ref "L1") (pin "1") (pinfunction "1_1") (pintype "input"))
      (node (ref "R13") (pin "2") (pinfunction "2_2") (pintype "input"))
      (node (ref "U1") (pin "1") (pinfunction "VDD_1") (pintype "input"))
      (node (ref "U1") (pin "24") (pinfunction "VDD_24") (pintype "input"))
      (node (ref "U1") (pin "48") (pinfunction "VDD_48") (pintype "input"))
    )
    (net (code "107") (name "VDDA") (class "Default")
      (node (ref "C27") (pin "2") (pinfunction "2_2") (pintype "input"))
      (node (ref "C28") (pin "2") (pinfunction "2_2") (pintype "input"))
      (node (ref "J3") (pin "8") (pinfunction "8_8") (pintype "input"))
      (node (ref "L1") (pin "2") (pinfunction "2_2") (pintype "input"))
      (node (ref "U1") (pin "9") (pinfunction "VDDA_9") (pintype "input"))
    )
    (net (code "108") (name "VDD_MCU") (class "Default")
      (node (ref "C34") (pin "2") (pinfunction "2_2") (pintype "input"))
      (node (ref "J4") (pin "2") (pinfunction "2_2") (pintype "input"))
      (node (ref "J4") (pin "4") (pinfunction "4_4") (pintype "input"))
      (node (ref "J8") (pin "1") (pinfunction "1_1") (pintype "input"))
      (node (ref "JP2") (pin "2") (pinfunction "2_2") (pintype "input"))
      (node (ref "JP3") (pin "1") (pinfunction "1_1") (pintype "input"))
      (node (ref "R13") (pin "1") (pinfunction "1_1") (pintype "input"))
      (node (ref "U4") (pin "1") (pinfunction "VCCA_1") (pintype "unspecified"))
      (node (ref "U4") (pin "8") (pinfunction "OE_8") (pintype "unspecified"))
    )
    (net (code "109") (name "unconnected-(CN2-Pad4)") (class "Default")
      (node (ref "CN2") (pin "4") (pinfunction "4_4") (pintype "input+no_connect"))
    )
    (net (code "110") (name "unconnected-(CN2-Pad6)") (class "Default")
      (node (ref "CN2") (pin "6") (pinfunction "6_6") (pintype "input+no_connect"))
    )
    (net (code "111") (name "unconnected-(CN6-SBU1-PadA8)") (class "Default")
      (node (ref "CN6") (pin "A8") (pinfunction "SBU1_A8") (pintype "input+no_connect"))
    )
    (net (code "112") (name "unconnected-(CN6-SBU2-PadB8)") (class "Default")
      (node (ref "CN6") (pin "B8") (pinfunction "SBU2_B8") (pintype "input+no_connect"))
    )
    (net (code "113") (name "unconnected-(J2-Pad8)") (class "Default")
      (node (ref "J2") (pin "8") (pinfunction "8_8") (pintype "input+no_connect"))
    )
    (net (code "114") (name "unconnected-(J2-Pad9)") (class "Default")
      (node (ref "J2") (pin "9") (pinfunction "9_9") (pintype "input+no_connect"))
    )
    (net (code "115") (name "unconnected-(J4-Pad1)") (class "Default")
      (node (ref "J4") (pin "1") (pinfunction "1_1") (pintype "input+no_connect"))
    )
    (net (code "116") (name "unconnected-(J4-Pad8)") (class "Default")
      (node (ref "J4") (pin "8") (pinfunction "8_8") (pintype "input+no_connect"))
    )
    (net (code "117") (name "unconnected-(RP2-Pad3)") (class "Default")
      (node (ref "RP2") (pin "3") (pinfunction "3_3") (pintype "input+no_connect"))
    )
    (net (code "118") (name "unconnected-(RP3-Pad3)") (class "Default")
      (node (ref "RP3") (pin "3") (pinfunction "3_3") (pintype "input+no_connect"))
    )
    (net (code "119") (name "unconnected-(RP3-Pad4)") (class "Default")
      (node (ref "RP3") (pin "4") (pinfunction "4_4") (pintype "input+no_connect"))
    )
    (net (code "120") (name "unconnected-(RP3-Pad5)") (class "Default")
      (node (ref "RP3") (pin "5") (pinfunction "5_5") (pintype "input+no_connect"))
    )
    (net (code "121") (name "unconnected-(U3-NC-Pad4)") (class "Default")
      (node (ref "U3") (pin "4") (pinfunction "NC_4") (pintype "input+no_connect"))
    )
    (net (code "122") (name "unconnected-(U4-NC-Pad6)") (class "Default")
      (node (ref "U4") (pin "6") (pinfunction "NC_6") (pintype "unspecified+no_connect"))
    )
    (net (code "123") (name "unconnected-(U4-NC-Pad9)") (class "Default")
      (node (ref "U4") (pin "9") (pinfunction "NC_9") (pintype "unspecified+no_connect"))
    )
    (net (code "124") (name "unconnected-(U6-PA4-Pad14)") (class "Default")
      (node (ref "U6") (pin "14") (pinfunction "PA4_14") (pintype "input+no_connect"))
    )
    (net (code "125") (name "unconnected-(U6-PA5-Pad15)") (class "Default")
      (node (ref "U6") (pin "15") (pinfunction "PA5_15") (pintype "input+no_connect"))
    )
    (net (code "126") (name "unconnected-(U6-PA6-Pad16)") (class "Default")
      (node (ref "U6") (pin "16") (pinfunction "PA6_16") (pintype "input+no_connect"))
    )
    (net (code "127") (name "unconnected-(U6-PA7-Pad17)") (class "Default")
      (node (ref "U6") (pin "17") (pinfunction "PA7_17") (pintype "input+no_connect"))
    )
    (net (code "128") (name "unconnected-(U6-PA8-Pad29)") (class "Default")
      (node (ref "U6") (pin "29") (pinfunction "PA8_29") (pintype "input+no_connect"))
    )
    (net (code "129") (name "unconnected-(U6-PA15-Pad38)") (class "Default")
      (node (ref "U6") (pin "38") (pinfunction "PA15_38") (pintype "input+no_connect"))
    )
    (net (code "130") (name "unconnected-(U6-PB0-Pad18)") (class "Default")
      (node (ref "U6") (pin "18") (pinfunction "PB0_18") (pintype "input+no_connect"))
    )
    (net (code "131") (name "unconnected-(U6-PB5-Pad41)") (class "Default")
      (node (ref "U6") (pin "41") (pinfunction "PB5_41") (pintype "input+no_connect"))
    )
    (net (code "132") (name "unconnected-(U6-PB6-Pad42)") (class "Default")
      (node (ref "U6") (pin "42") (pinfunction "PB6_42") (pintype "input+no_connect"))
    )
    (net (code "133") (name "unconnected-(U6-PB7-Pad43)") (class "Default")
      (node (ref "U6") (pin "43") (pinfunction "PB7_43") (pintype "input+no_connect"))
    )
    (net (code "134") (name "unconnected-(U6-PB8-Pad45)") (class "Default")
      (node (ref "U6") (pin "45") (pinfunction "PB8_45") (pintype "input+no_connect"))
    )
    (net (code "135") (name "unconnected-(U6-PB9-Pad46)") (class "Default")
      (node (ref "U6") (pin "46") (pinfunction "PB9_46") (pintype "input+no_connect"))
    )
    (net (code "136") (name "unconnected-(U6-PB10-Pad21)") (class "Default")
      (node (ref "U6") (pin "21") (pinfunction "PB10_21") (pintype "input+no_connect"))
    )
    (net (code "137") (name "unconnected-(U6-PB11-Pad22)") (class "Default")
      (node (ref "U6") (pin "22") (pinfunction "PB11_22") (pintype "input+no_connect"))
    )
    (net (code "138") (name "unconnected-(U6-PC13-TAMPER-RTC-Pad2)") (class "Default")
      (node (ref "U6") (pin "2") (pinfunction "PC13-TAMPER-RTC_2") (pintype "input+no_connect"))
    )
    (net (code "139") (name "unconnected-(U6-PC14{slash}LEXT_IN-Pad3)") (class "Default")
      (node (ref "U6") (pin "3") (pinfunction "PC14/LEXT_IN_3") (pintype "input+no_connect"))
    )
    (net (code "140") (name "unconnected-(U6-PC15{slash}LEXT_OUT-Pad4)") (class "Default")
      (node (ref "U6") (pin "4") (pinfunction "PC15/LEXT_OUT_4") (pintype "input+no_connect"))
    )
    (net (code "141") (name "unconnected-(U6-PD0{slash}HEXT_IN-Pad5)") (class "Default")
      (node (ref "U6") (pin "5") (pinfunction "PD0/HEXT_IN_5") (pintype "input+no_connect"))
    )
    (net (code "142") (name "unconnected-(U6-PD1{slash}HEXT_OUT-Pad6)") (class "Default")
      (node (ref "U6") (pin "6") (pinfunction "PD1/HEXT_OUT_6") (pintype "input+no_connect"))
    )
  )
)
